# PCB0M3_1C.net
KiCad netlist of a schematic drawn in EAGLE
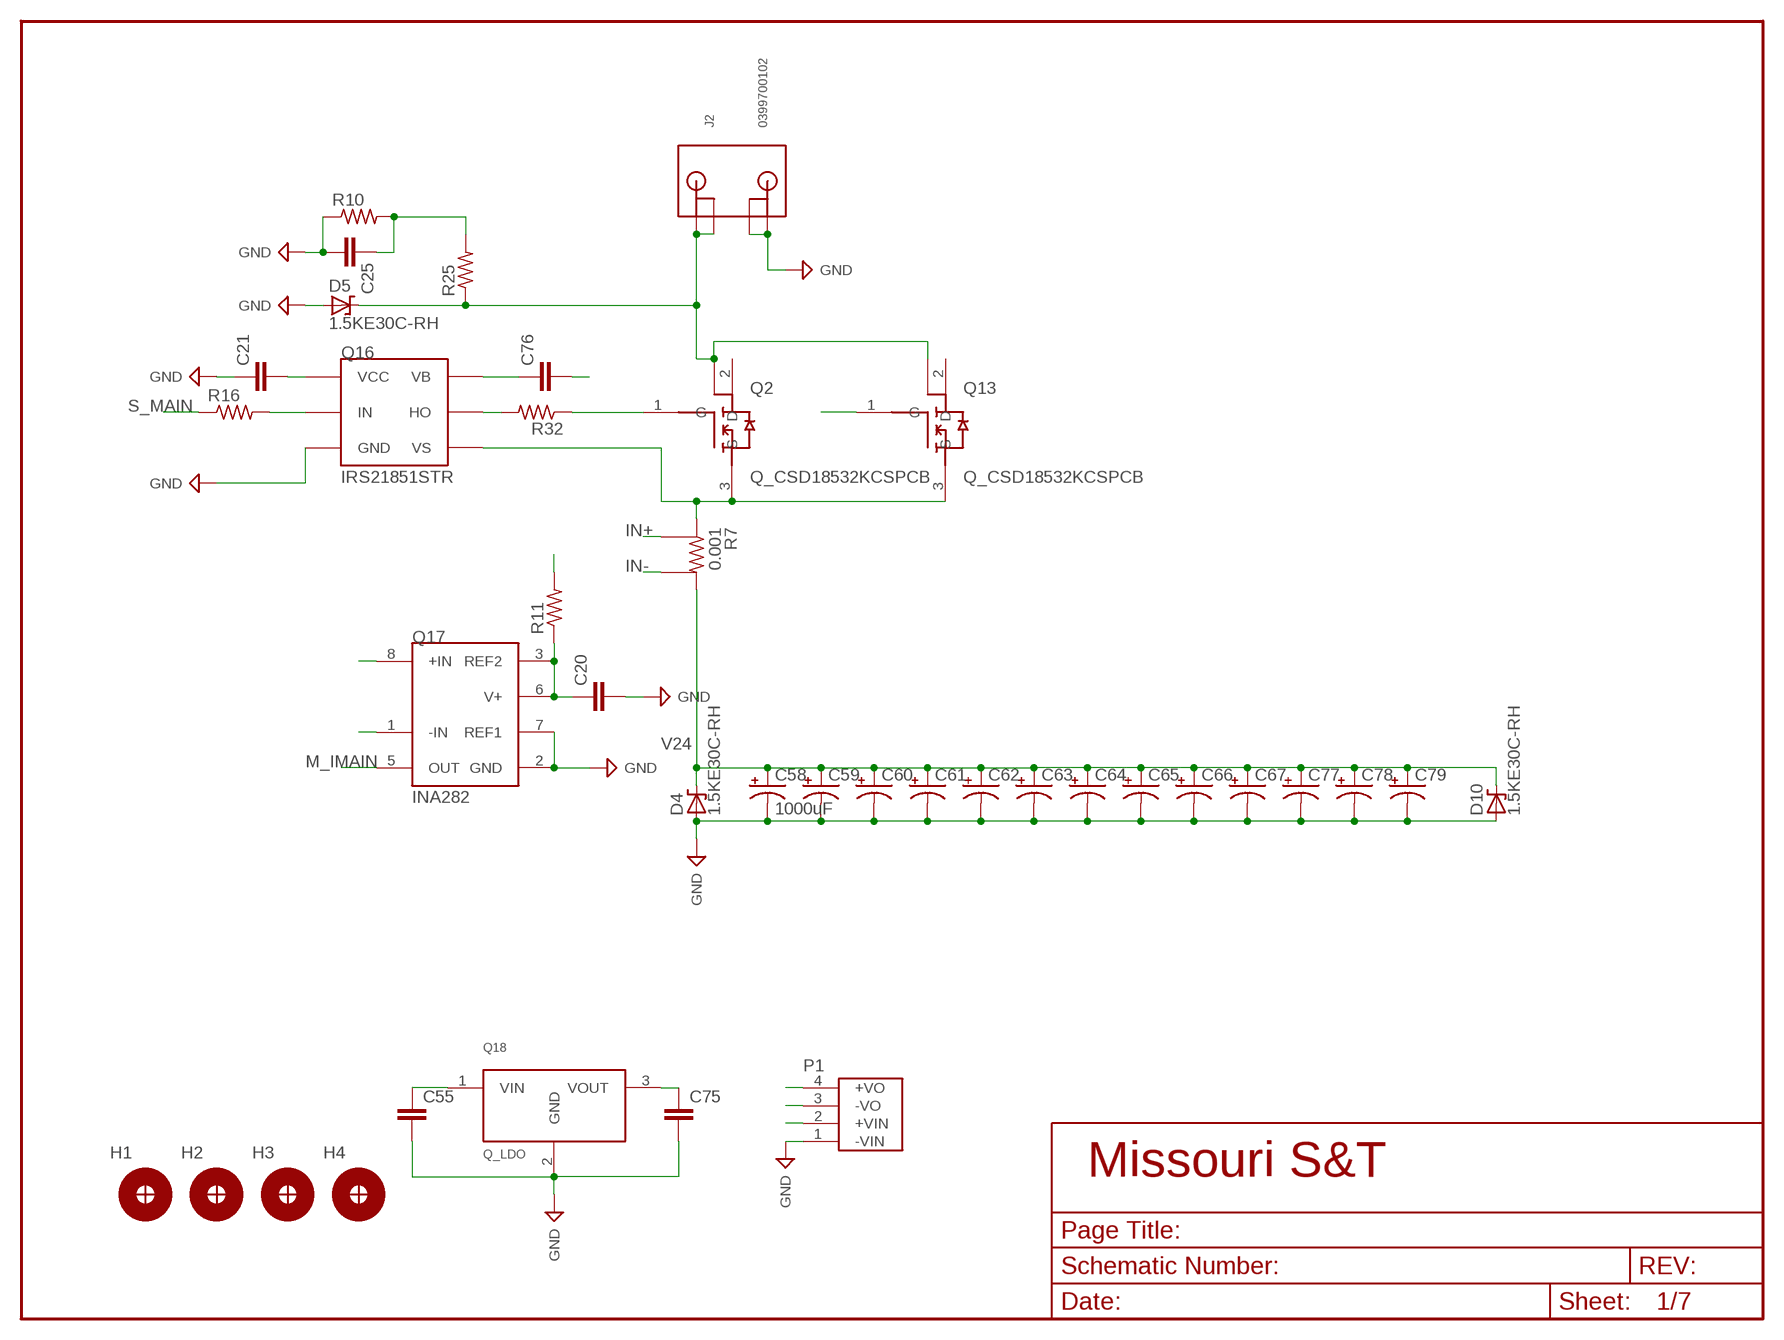
[diagram p0: schematic, sheet 1]
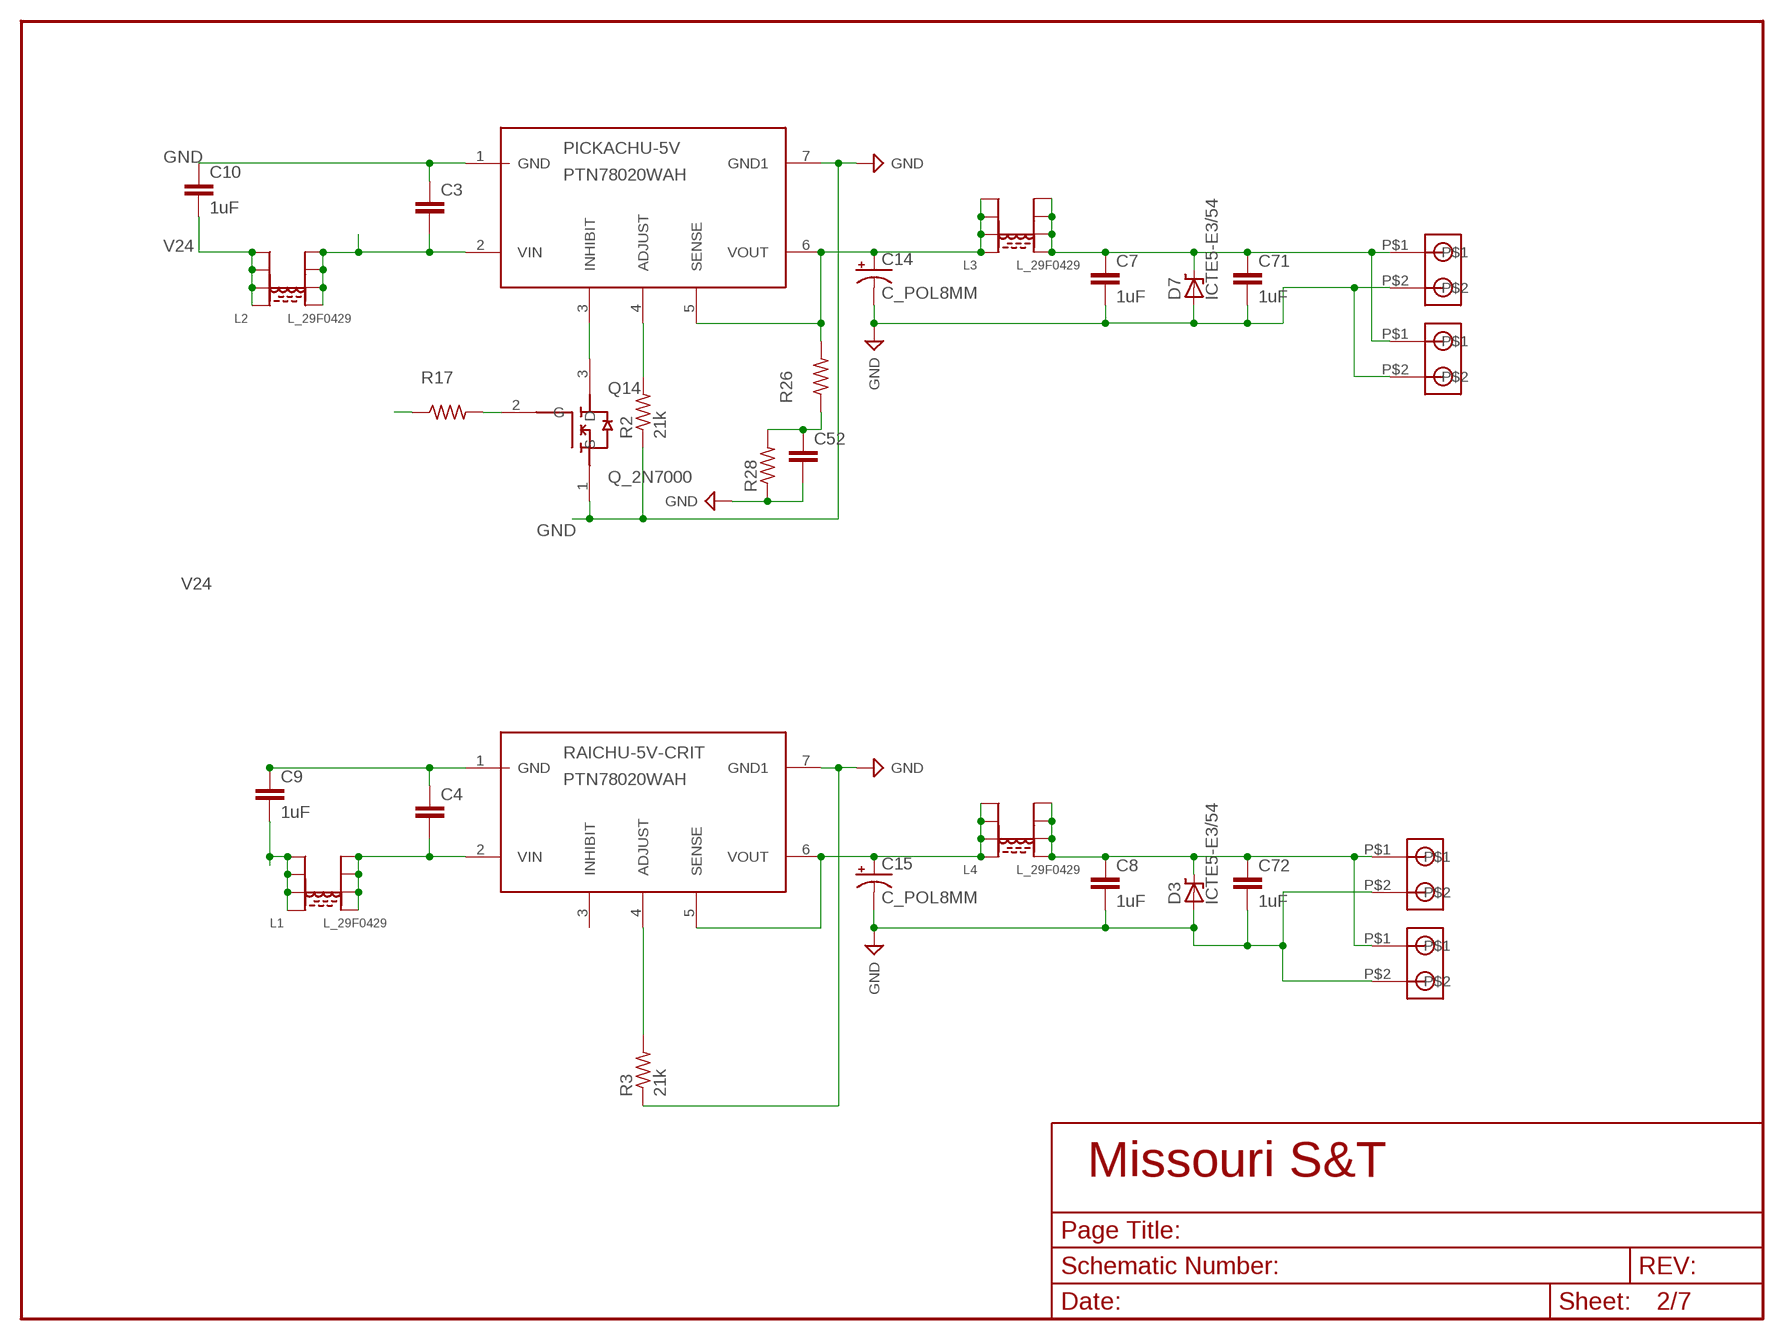
[diagram p1: schematic, sheet 2]
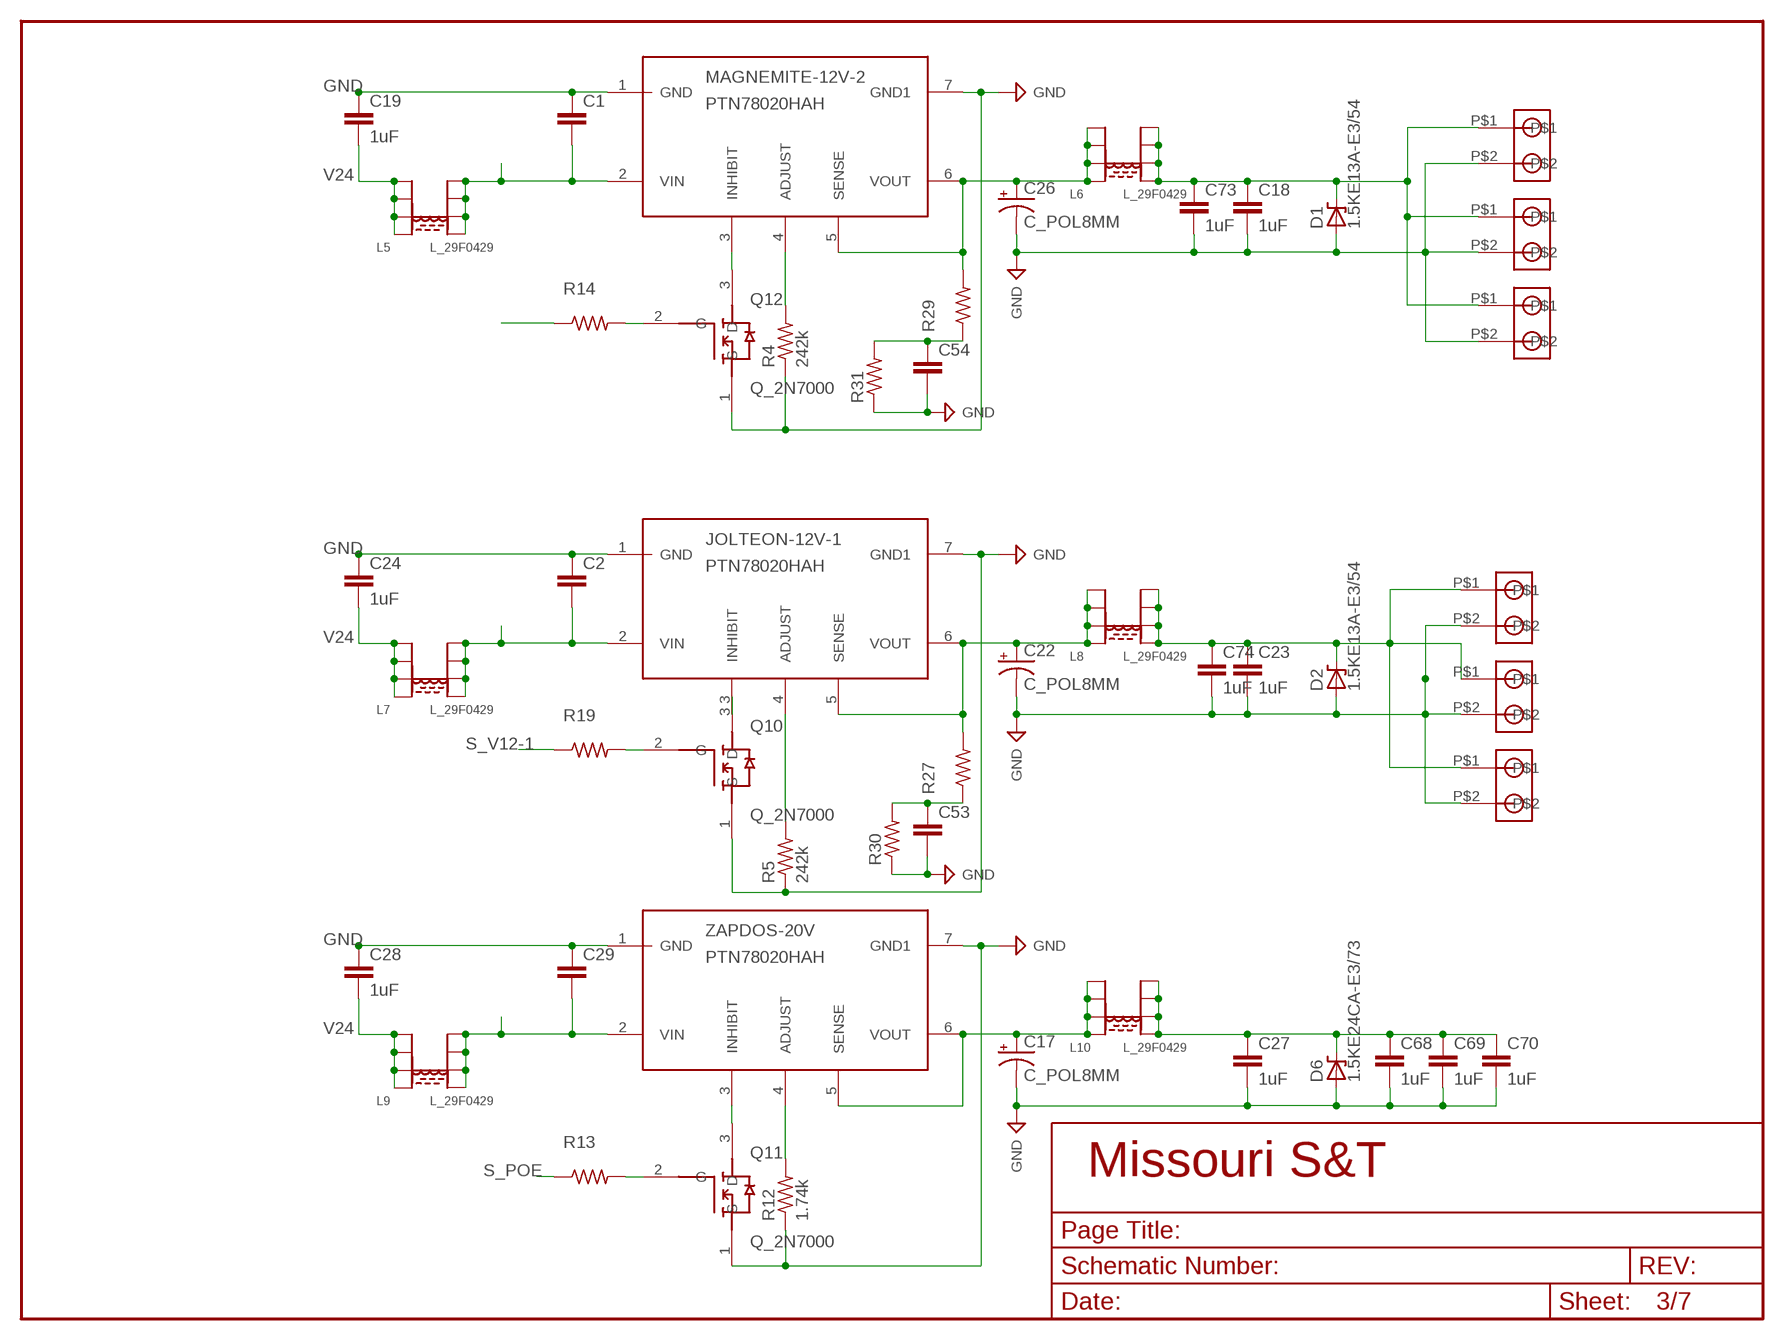
[diagram p2: schematic, sheet 3]
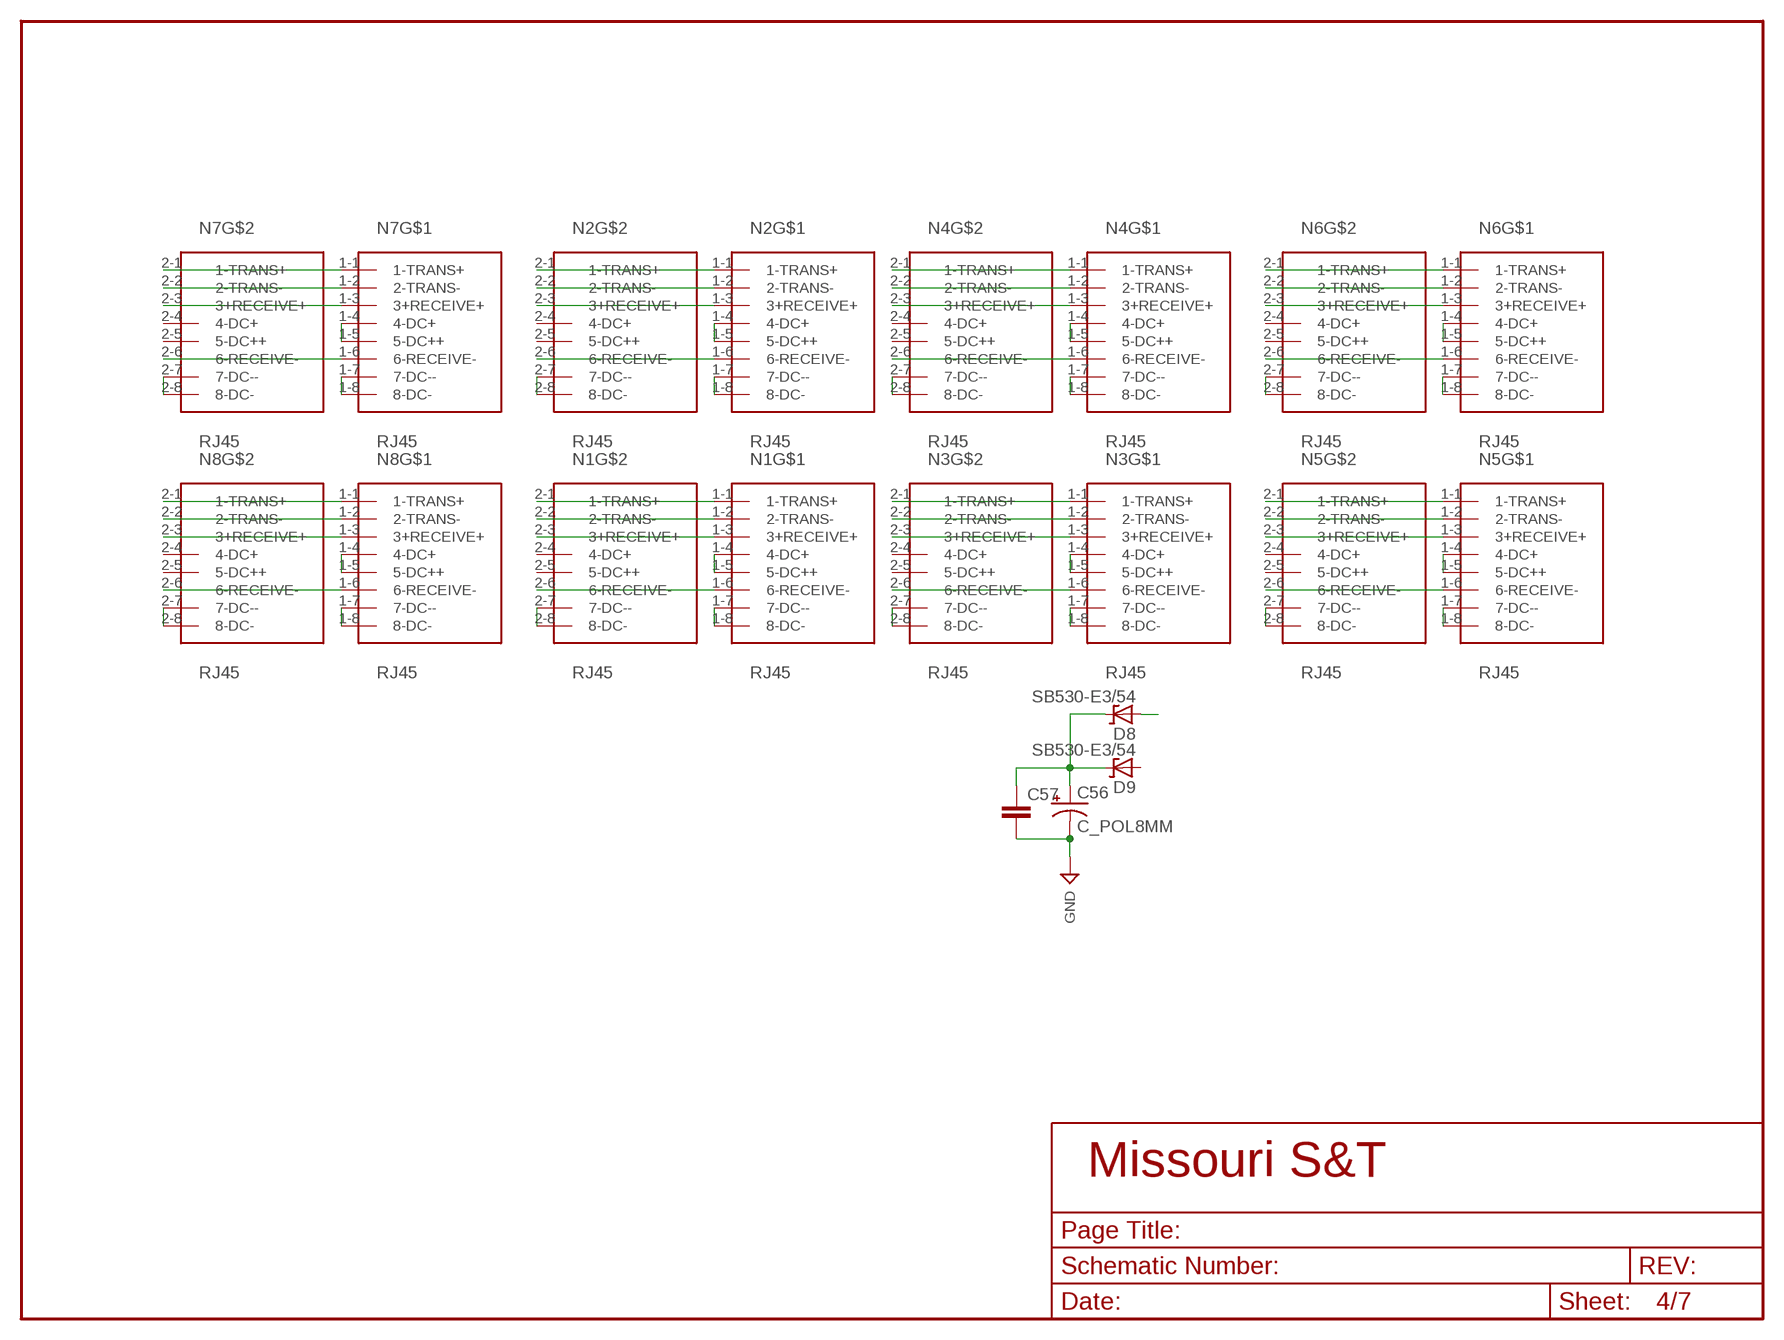
[diagram p3: schematic, sheet 4]
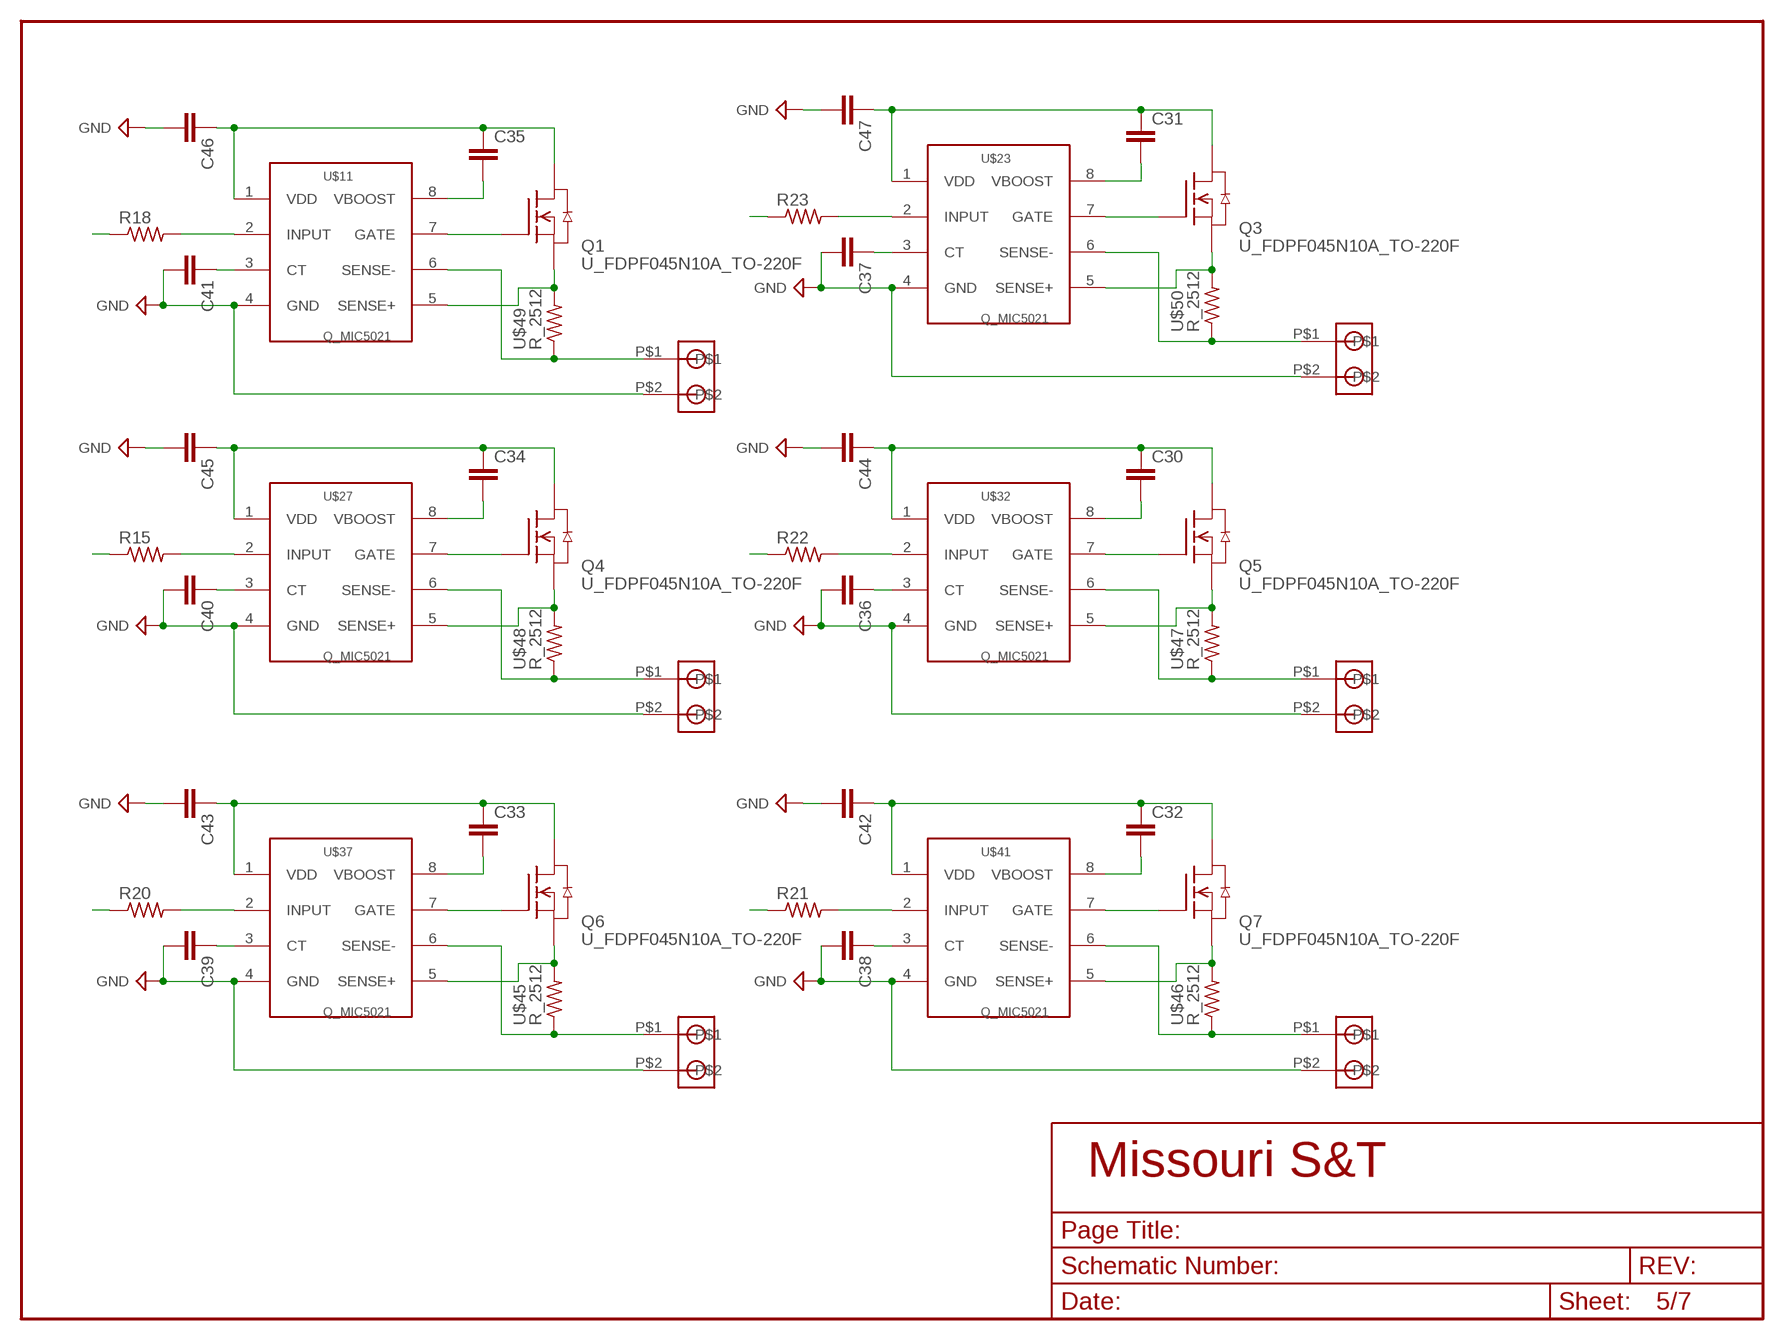
[diagram p4: schematic, sheet 5]
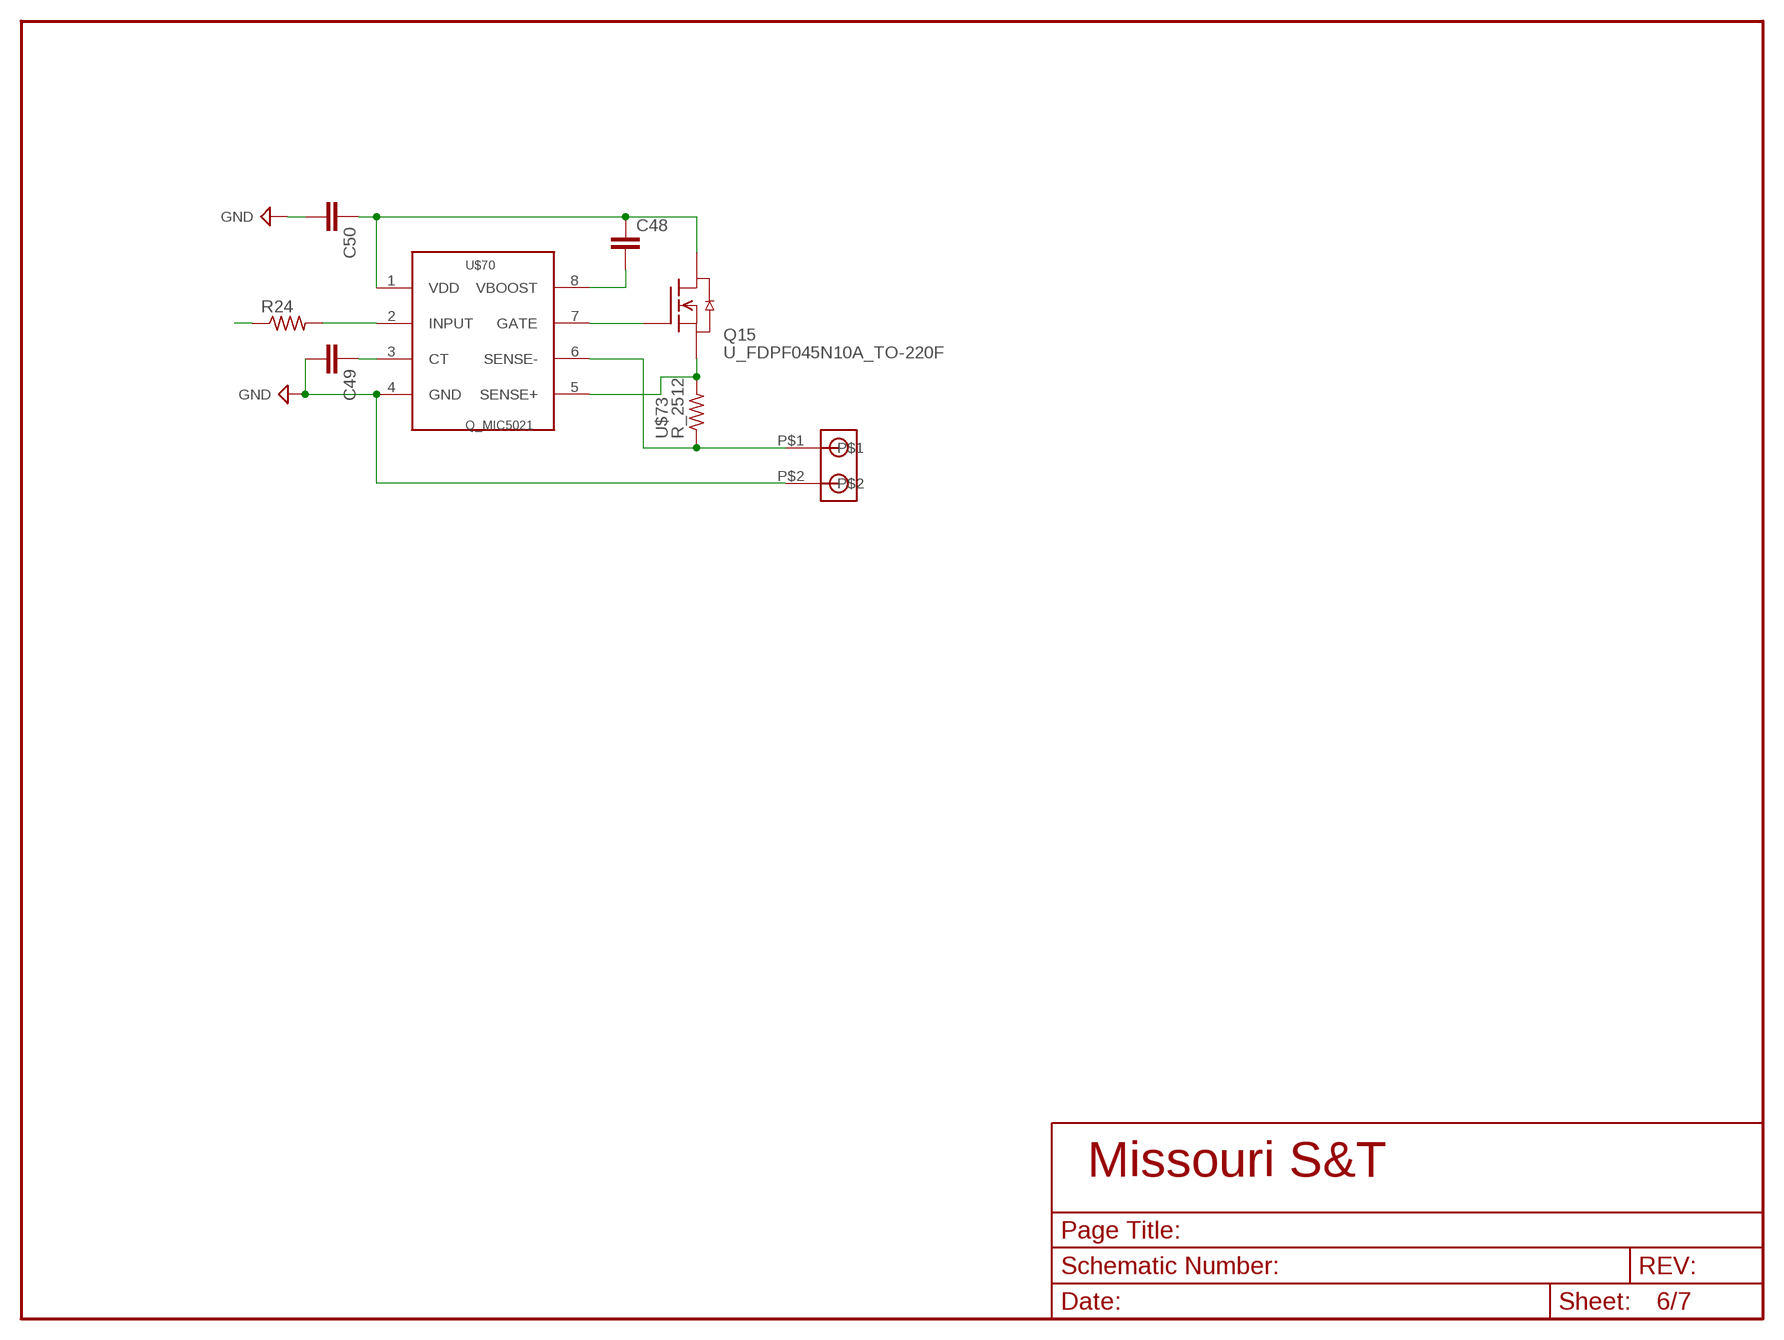
[diagram p5: schematic, sheet 6]
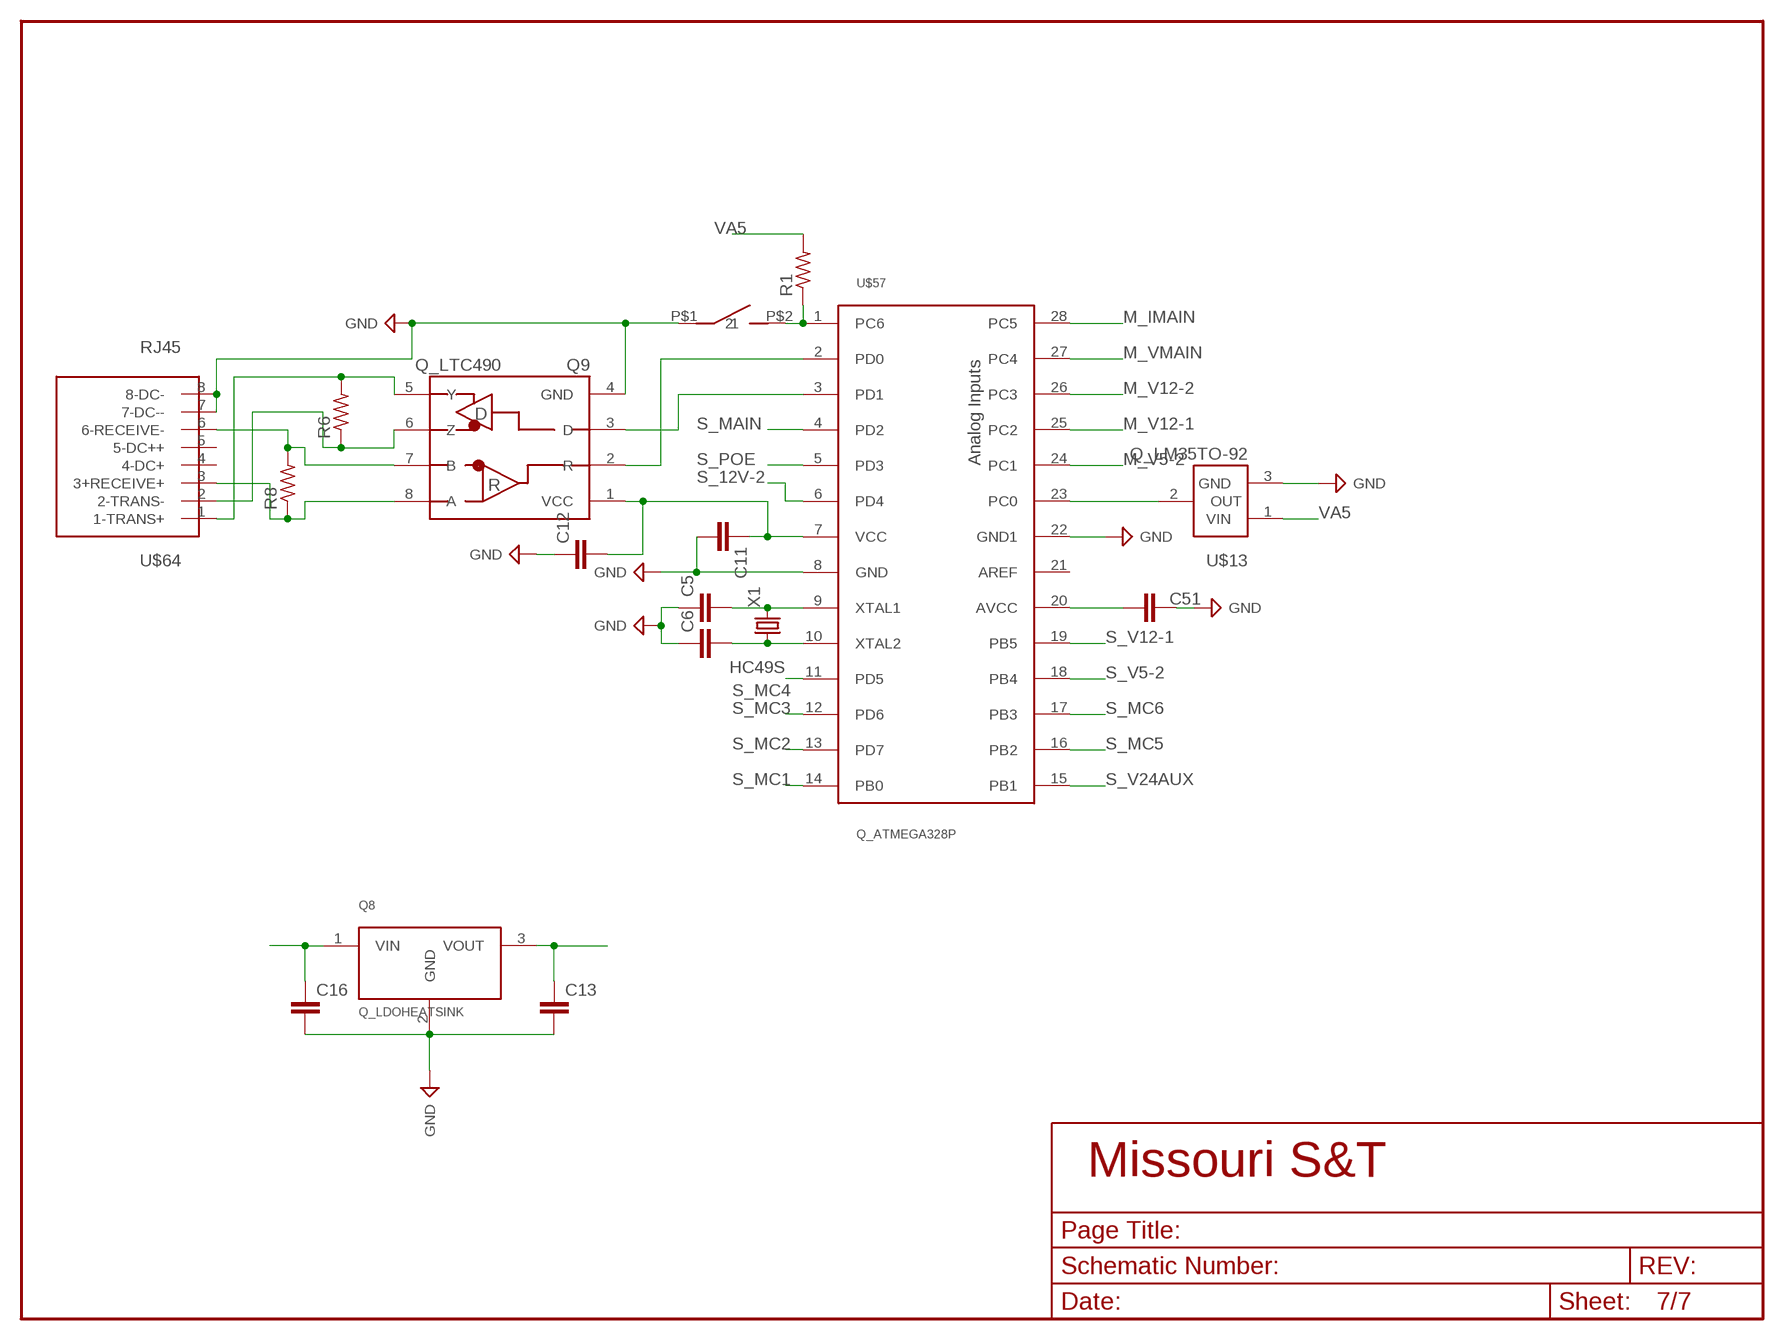
[diagram p6: schematic, sheet 7]

(export (version "E")
  (design (tool "Eeschema 10.0.6"))
  (components
    (comp (ref "C3")
      (value "C_CAP_1206")
      (footprint "eagle-import:C_1206")
      (libsource (lib "eagle-import") (part "C_CAP_1206"))
    )
    (comp (ref "C4")
      (value "C_CAP_1206")
      (footprint "eagle-import:C_1206")
      (libsource (lib "eagle-import") (part "C_CAP_1206"))
    )
    (comp (ref "C7")
      (value "1uF")
      (footprint "eagle-import:C_1206")
      (libsource (lib "eagle-import") (part "C_CAP_1206"))
    )
    (comp (ref "C8")
      (value "1uF")
      (footprint "eagle-import:C_1206")
      (libsource (lib "eagle-import") (part "C_CAP_1206"))
    )
    (comp (ref "C9")
      (value "1uF")
      (footprint "eagle-import:C_1206")
      (libsource (lib "eagle-import") (part "C_CAP_1206"))
    )
    (comp (ref "C10")
      (value "1uF")
      (footprint "eagle-import:C_1206")
      (libsource (lib "eagle-import") (part "C_CAP_1206"))
    )
    (comp (ref "C14")
      (value "C_POL8MM")
      (footprint "eagle-import:C_8MM")
      (libsource (lib "eagle-import") (part "C_POL8MM"))
    )
    (comp (ref "C15")
      (value "C_POL8MM")
      (footprint "eagle-import:C_8MM")
      (libsource (lib "eagle-import") (part "C_POL8MM"))
    )
    (comp (ref "C52")
      (value "C_CAP_1206")
      (footprint "eagle-import:C_1206")
      (libsource (lib "eagle-import") (part "C_CAP_1206"))
    )
    (comp (ref "C71")
      (value "1uF")
      (footprint "eagle-import:C_1206")
      (libsource (lib "eagle-import") (part "C_CAP_1206"))
    )
    (comp (ref "C72")
      (value "1uF")
      (footprint "eagle-import:C_1206")
      (libsource (lib "eagle-import") (part "C_CAP_1206"))
    )
    (comp (ref "D3")
      (value "ICTE5-E3/54")
      (footprint "eagle-import:DIODE_D3.5MM_LS15.24MM")
      (libsource (lib "eagle-import") (part "D_1.5KE480A_D3.5MM_LS15.24MM"))
    )
    (comp (ref "D7")
      (value "ICTE5-E3/54")
      (footprint "eagle-import:DIODE_D3.5MM_LS15.24MM")
      (libsource (lib "eagle-import") (part "D_1.5KE480A_D3.5MM_LS15.24MM"))
    )
    (comp (ref "L1")
      (value "L_29F0429")
      (footprint "eagle-import:L_29F0429")
      (libsource (lib "eagle-import") (part "L_29F0429"))
    )
    (comp (ref "L2")
      (value "L_29F0429")
      (footprint "eagle-import:L_29F0429")
      (libsource (lib "eagle-import") (part "L_29F0429"))
    )
    (comp (ref "L3")
      (value "L_29F0429")
      (footprint "eagle-import:L_29F0429")
      (libsource (lib "eagle-import") (part "L_29F0429"))
    )
    (comp (ref "L4")
      (value "L_29F0429")
      (footprint "eagle-import:L_29F0429")
      (libsource (lib "eagle-import") (part "L_29F0429"))
    )
    (comp (ref "PICKACHU-5V")
      (value "PTN78020WAH")
      (footprint "eagle-import:R_PDSS-T7")
      (libsource (lib "eagle-import") (part "Q_PTN78020"))
    )
    (comp (ref "Q14")
      (value "Q_2N7000")
      (footprint "eagle-import:TO-92-3")
      (libsource (lib "eagle-import") (part "Q_2N7000"))
    )
    (comp (ref "R2")
      (value "21k")
      (footprint "eagle-import:R_1_4W")
      (libsource (lib "eagle-import") (part "R_1/4W"))
    )
    (comp (ref "R3")
      (value "21k")
      (footprint "eagle-import:R_1_4W")
      (libsource (lib "eagle-import") (part "R_1/4W"))
    )
    (comp (ref "R17")
      (value "R_1/4WL")
      (footprint "eagle-import:R_1_4WL")
      (libsource (lib "eagle-import") (part "R_1/4WL"))
    )
    (comp (ref "R26")
      (value "R_1/4WL")
      (footprint "eagle-import:R_1_4WL")
      (libsource (lib "eagle-import") (part "R_1/4WL"))
    )
    (comp (ref "R28")
      (value "R_RES_1206")
      (footprint "eagle-import:R_1206")
      (libsource (lib "eagle-import") (part "R_RES_1206"))
    )
    (comp (ref "RAICHU-5V-CRIT")
      (value "PTN78020WAH")
      (footprint "eagle-import:R_PDSS-T7")
      (libsource (lib "eagle-import") (part "Q_PTN78020"))
    )
    (comp (ref "U$52")
      (value "J_1546074-2282834-2")
      (footprint "eagle-import:J_2.54MM")
      (libsource (lib "eagle-import") (part "J_1546074-2282834-2"))
    )
    (comp (ref "U$53")
      (value "J_1546074-2282834-2")
      (footprint "eagle-import:J_2.54MM")
      (libsource (lib "eagle-import") (part "J_1546074-2282834-2"))
    )
    (comp (ref "U$54")
      (value "J_1546074-2282834-2")
      (footprint "eagle-import:J_2.54MM")
      (libsource (lib "eagle-import") (part "J_1546074-2282834-2"))
    )
    (comp (ref "U$55")
      (value "J_1546074-2282834-2")
      (footprint "eagle-import:J_2.54MM")
      (libsource (lib "eagle-import") (part "J_1546074-2282834-2"))
    )
    (comp (ref "C30")
      (value "C_CAP_1206")
      (footprint "eagle-import:C_1206")
      (libsource (lib "eagle-import") (part "C_CAP_1206"))
    )
    (comp (ref "C31")
      (value "C_CAP_1206")
      (footprint "eagle-import:C_1206")
      (libsource (lib "eagle-import") (part "C_CAP_1206"))
    )
    (comp (ref "C32")
      (value "C_CAP_1206")
      (footprint "eagle-import:C_1206")
      (libsource (lib "eagle-import") (part "C_CAP_1206"))
    )
    (comp (ref "C33")
      (value "C_CAP_1206")
      (footprint "eagle-import:C_1206")
      (libsource (lib "eagle-import") (part "C_CAP_1206"))
    )
    (comp (ref "C34")
      (value "C_CAP_1206")
      (footprint "eagle-import:C_1206")
      (libsource (lib "eagle-import") (part "C_CAP_1206"))
    )
    (comp (ref "C35")
      (value "C_CAP_1206")
      (footprint "eagle-import:C_1206")
      (libsource (lib "eagle-import") (part "C_CAP_1206"))
    )
    (comp (ref "C36")
      (value "C_CAP_1206")
      (footprint "eagle-import:C_1206")
      (libsource (lib "eagle-import") (part "C_CAP_1206"))
    )
    (comp (ref "C37")
      (value "C_CAP_1206")
      (footprint "eagle-import:C_1206")
      (libsource (lib "eagle-import") (part "C_CAP_1206"))
    )
    (comp (ref "C38")
      (value "C_CAP_1206")
      (footprint "eagle-import:C_1206")
      (libsource (lib "eagle-import") (part "C_CAP_1206"))
    )
    (comp (ref "C39")
      (value "C_CAP_1206")
      (footprint "eagle-import:C_1206")
      (libsource (lib "eagle-import") (part "C_CAP_1206"))
    )
    (comp (ref "C40")
      (value "C_CAP_1206")
      (footprint "eagle-import:C_1206")
      (libsource (lib "eagle-import") (part "C_CAP_1206"))
    )
    (comp (ref "C41")
      (value "C_CAP_1206")
      (footprint "eagle-import:C_1206")
      (libsource (lib "eagle-import") (part "C_CAP_1206"))
    )
    (comp (ref "C42")
      (value "C_CAP_1206")
      (footprint "eagle-import:C_1206")
      (libsource (lib "eagle-import") (part "C_CAP_1206"))
    )
    (comp (ref "C43")
      (value "C_CAP_1206")
      (footprint "eagle-import:C_1206")
      (libsource (lib "eagle-import") (part "C_CAP_1206"))
    )
    (comp (ref "C44")
      (value "C_CAP_1206")
      (footprint "eagle-import:C_1206")
      (libsource (lib "eagle-import") (part "C_CAP_1206"))
    )
    (comp (ref "C45")
      (value "C_CAP_1206")
      (footprint "eagle-import:C_1206")
      (libsource (lib "eagle-import") (part "C_CAP_1206"))
    )
    (comp (ref "C46")
      (value "C_CAP_1206")
      (footprint "eagle-import:C_1206")
      (libsource (lib "eagle-import") (part "C_CAP_1206"))
    )
    (comp (ref "C47")
      (value "C_CAP_1206")
      (footprint "eagle-import:C_1206")
      (libsource (lib "eagle-import") (part "C_CAP_1206"))
    )
    (comp (ref "Q1")
      (value "U_FDPF045N10A_TO-220F")
      (footprint "eagle-import:TO220F")
      (libsource (lib "eagle-import") (part "U_FDPF045N10A_TO-220F"))
    )
    (comp (ref "Q3")
      (value "U_FDPF045N10A_TO-220F")
      (footprint "eagle-import:TO220F")
      (libsource (lib "eagle-import") (part "U_FDPF045N10A_TO-220F"))
    )
    (comp (ref "Q4")
      (value "U_FDPF045N10A_TO-220F")
      (footprint "eagle-import:TO220F")
      (libsource (lib "eagle-import") (part "U_FDPF045N10A_TO-220F"))
    )
    (comp (ref "Q5")
      (value "U_FDPF045N10A_TO-220F")
      (footprint "eagle-import:TO220F")
      (libsource (lib "eagle-import") (part "U_FDPF045N10A_TO-220F"))
    )
    (comp (ref "Q6")
      (value "U_FDPF045N10A_TO-220F")
      (footprint "eagle-import:TO220F")
      (libsource (lib "eagle-import") (part "U_FDPF045N10A_TO-220F"))
    )
    (comp (ref "Q7")
      (value "U_FDPF045N10A_TO-220F")
      (footprint "eagle-import:TO220F")
      (libsource (lib "eagle-import") (part "U_FDPF045N10A_TO-220F"))
    )
    (comp (ref "R15")
      (value "R_RES_1206")
      (footprint "eagle-import:R_1206")
      (libsource (lib "eagle-import") (part "R_RES_1206"))
    )
    (comp (ref "R18")
      (value "R_RES_1206")
      (footprint "eagle-import:R_1206")
      (libsource (lib "eagle-import") (part "R_RES_1206"))
    )
    (comp (ref "R20")
      (value "R_RES_1206")
      (footprint "eagle-import:R_1206")
      (libsource (lib "eagle-import") (part "R_RES_1206"))
    )
    (comp (ref "R21")
      (value "R_RES_1206")
      (footprint "eagle-import:R_1206")
      (libsource (lib "eagle-import") (part "R_RES_1206"))
    )
    (comp (ref "R22")
      (value "R_RES_1206")
      (footprint "eagle-import:R_1206")
      (libsource (lib "eagle-import") (part "R_RES_1206"))
    )
    (comp (ref "R23")
      (value "R_RES_1206")
      (footprint "eagle-import:R_1206")
      (libsource (lib "eagle-import") (part "R_RES_1206"))
    )
    (comp (ref "U$11")
      (value "Q_MIC5021")
      (footprint "eagle-import:DIP8")
      (libsource (lib "eagle-import") (part "Q_MIC5021"))
    )
    (comp (ref "U$14")
      (value "J_1546074-2")
      (footprint "eagle-import:THERM_BLOCK_2")
      (libsource (lib "eagle-import") (part "J_1546074-2"))
    )
    (comp (ref "U$23")
      (value "Q_MIC5021")
      (footprint "eagle-import:DIP8")
      (libsource (lib "eagle-import") (part "Q_MIC5021"))
    )
    (comp (ref "U$26")
      (value "J_1546074-2")
      (footprint "eagle-import:THERM_BLOCK_2")
      (libsource (lib "eagle-import") (part "J_1546074-2"))
    )
    (comp (ref "U$27")
      (value "Q_MIC5021")
      (footprint "eagle-import:DIP8")
      (libsource (lib "eagle-import") (part "Q_MIC5021"))
    )
    (comp (ref "U$31")
      (value "J_1546074-2")
      (footprint "eagle-import:THERM_BLOCK_2")
      (libsource (lib "eagle-import") (part "J_1546074-2"))
    )
    (comp (ref "U$32")
      (value "Q_MIC5021")
      (footprint "eagle-import:DIP8")
      (libsource (lib "eagle-import") (part "Q_MIC5021"))
    )
    (comp (ref "U$36")
      (value "J_1546074-2")
      (footprint "eagle-import:THERM_BLOCK_2")
      (libsource (lib "eagle-import") (part "J_1546074-2"))
    )
    (comp (ref "U$37")
      (value "Q_MIC5021")
      (footprint "eagle-import:DIP8")
      (libsource (lib "eagle-import") (part "Q_MIC5021"))
    )
    (comp (ref "U$40")
      (value "J_1546074-2")
      (footprint "eagle-import:THERM_BLOCK_2")
      (libsource (lib "eagle-import") (part "J_1546074-2"))
    )
    (comp (ref "U$41")
      (value "Q_MIC5021")
      (footprint "eagle-import:DIP8")
      (libsource (lib "eagle-import") (part "Q_MIC5021"))
    )
    (comp (ref "U$44")
      (value "J_1546074-2")
      (footprint "eagle-import:THERM_BLOCK_2")
      (libsource (lib "eagle-import") (part "J_1546074-2"))
    )
    (comp (ref "U$45")
      (value "R_2512")
      (footprint "eagle-import:R_2512")
      (libsource (lib "eagle-import") (part "R_2512"))
    )
    (comp (ref "U$46")
      (value "R_2512")
      (footprint "eagle-import:R_2512")
      (libsource (lib "eagle-import") (part "R_2512"))
    )
    (comp (ref "U$47")
      (value "R_2512")
      (footprint "eagle-import:R_2512")
      (libsource (lib "eagle-import") (part "R_2512"))
    )
    (comp (ref "U$48")
      (value "R_2512")
      (footprint "eagle-import:R_2512")
      (libsource (lib "eagle-import") (part "R_2512"))
    )
    (comp (ref "U$49")
      (value "R_2512")
      (footprint "eagle-import:R_2512")
      (libsource (lib "eagle-import") (part "R_2512"))
    )
    (comp (ref "U$50")
      (value "R_2512")
      (footprint "eagle-import:R_2512")
      (libsource (lib "eagle-import") (part "R_2512"))
    )
    (comp (ref "C20")
      (value "C_CAP_1206")
      (footprint "eagle-import:C_1206")
      (libsource (lib "eagle-import") (part "C_CAP_1206"))
    )
    (comp (ref "C21")
      (value "C_CAP_1206")
      (footprint "eagle-import:C_1206")
      (libsource (lib "eagle-import") (part "C_CAP_1206"))
    )
    (comp (ref "C25")
      (value "C_CAP_1206")
      (footprint "eagle-import:C_1206")
      (libsource (lib "eagle-import") (part "C_CAP_1206"))
    )
    (comp (ref "C55")
      (value "C_CAP_1206")
      (footprint "eagle-import:C_1206")
      (libsource (lib "eagle-import") (part "C_CAP_1206"))
    )
    (comp (ref "C58")
      (value "1000uF")
      (footprint "eagle-import:C_10MM")
      (libsource (lib "eagle-import") (part "C_POL10MM"))
    )
    (comp (ref "C59")
      (value "C_POL10MM")
      (footprint "eagle-import:C_10MM")
      (libsource (lib "eagle-import") (part "C_POL10MM"))
    )
    (comp (ref "C60")
      (value "C_POL10MM")
      (footprint "eagle-import:C_10MM")
      (libsource (lib "eagle-import") (part "C_POL10MM"))
    )
    (comp (ref "C61")
      (value "C_POL10MM")
      (footprint "eagle-import:C_10MM")
      (libsource (lib "eagle-import") (part "C_POL10MM"))
    )
    (comp (ref "C62")
      (value "C_POL10MM")
      (footprint "eagle-import:C_10MM")
      (libsource (lib "eagle-import") (part "C_POL10MM"))
    )
    (comp (ref "C63")
      (value "C_POL10MM")
      (footprint "eagle-import:C_10MM")
      (libsource (lib "eagle-import") (part "C_POL10MM"))
    )
    (comp (ref "C64")
      (value "C_POL10MM")
      (footprint "eagle-import:C_10MM")
      (libsource (lib "eagle-import") (part "C_POL10MM"))
    )
    (comp (ref "C65")
      (value "C_POL10MM")
      (footprint "eagle-import:C_10MM")
      (libsource (lib "eagle-import") (part "C_POL10MM"))
    )
    (comp (ref "C66")
      (value "C_POL10MM")
      (footprint "eagle-import:C_10MM")
      (libsource (lib "eagle-import") (part "C_POL10MM"))
    )
    (comp (ref "C67")
      (value "C_POL10MM")
      (footprint "eagle-import:C_10MM")
      (libsource (lib "eagle-import") (part "C_POL10MM"))
    )
    (comp (ref "C75")
      (value "C_CAP_1206")
      (footprint "eagle-import:C_1206")
      (libsource (lib "eagle-import") (part "C_CAP_1206"))
    )
    (comp (ref "C76")
      (value "C_CAP_1206")
      (footprint "eagle-import:C_1206")
      (libsource (lib "eagle-import") (part "C_CAP_1206"))
    )
    (comp (ref "C77")
      (value "C_POL10MM")
      (footprint "eagle-import:C_10MM")
      (libsource (lib "eagle-import") (part "C_POL10MM"))
    )
    (comp (ref "C78")
      (value "C_POL10MM")
      (footprint "eagle-import:C_10MM")
      (libsource (lib "eagle-import") (part "C_POL10MM"))
    )
    (comp (ref "C79")
      (value "C_POL10MM")
      (footprint "eagle-import:C_10MM")
      (libsource (lib "eagle-import") (part "C_POL10MM"))
    )
    (comp (ref "D4")
      (value "1.5KE30C-RH")
      (footprint "eagle-import:DIODE_D3.5MM_LS15.24MM")
      (libsource (lib "eagle-import") (part "D_1.5KE480A_D3.5MM_LS15.24MM"))
    )
    (comp (ref "D5")
      (value "1.5KE30C-RH")
      (footprint "eagle-import:DIODE_D3.5MM_LS15.24MM")
      (libsource (lib "eagle-import") (part "D_1.5KE480A_D3.5MM_LS15.24MM"))
    )
    (comp (ref "D10")
      (value "1.5KE30C-RH")
      (footprint "eagle-import:DIODE_D3.5MM_LS15.24MM")
      (libsource (lib "eagle-import") (part "D_1.5KE480A_D3.5MM_LS15.24MM"))
    )
    (comp (ref "H1")
      (value "H_MNTHOLE_#8")
      (footprint "eagle-import:H_MNTHOLE_#8")
      (libsource (lib "eagle-import") (part "H_MNTHOLE_#8"))
    )
    (comp (ref "H2")
      (value "H_MNTHOLE_#8")
      (footprint "eagle-import:H_MNTHOLE_#8")
      (libsource (lib "eagle-import") (part "H_MNTHOLE_#8"))
    )
    (comp (ref "H3")
      (value "H_MNTHOLE_#8")
      (footprint "eagle-import:H_MNTHOLE_#8")
      (libsource (lib "eagle-import") (part "H_MNTHOLE_#8"))
    )
    (comp (ref "H4")
      (value "H_MNTHOLE_#8")
      (footprint "eagle-import:H_MNTHOLE_#8")
      (libsource (lib "eagle-import") (part "H_MNTHOLE_#8"))
    )
    (comp (ref "J2")
      (value "0399700102")
      (footprint "eagle-import:J_2CONHC")
      (libsource (lib "eagle-import") (part "J_0399700102"))
    )
    (comp (ref "P1")
      (value "TME1215S")
      (footprint "eagle-import:TME1215S")
      (libsource (lib "eagle-import") (part "TME1215S"))
    )
    (comp (ref "Q2")
      (value "Q_CSD18532KCSPCB")
      (footprint "eagle-import:TO-220-FLAT")
      (libsource (lib "eagle-import") (part "Q_CSD18532KCSPCB"))
    )
    (comp (ref "Q13")
      (value "Q_CSD18532KCSPCB")
      (footprint "eagle-import:TO-220-FLAT")
      (libsource (lib "eagle-import") (part "Q_CSD18532KCSPCB"))
    )
    (comp (ref "Q16")
      (value "IRS21851STR")
      (footprint "eagle-import:SOIC8")
      (libsource (lib "eagle-import") (part "Q_IRS21851STR"))
    )
    (comp (ref "Q17")
      (value "INA282")
      (footprint "eagle-import:SOIC8")
      (libsource (lib "eagle-import") (part "Q_INA28"))
    )
    (comp (ref "Q18")
      (value "Q_LDO")
      (footprint "eagle-import:TO-220")
      (libsource (lib "eagle-import") (part "Q_LDO"))
    )
    (comp (ref "R7")
      (value "0.001")
      (footprint "eagle-import:R_FC4L")
      (libsource (lib "eagle-import") (part "R_FC4L110R001JER"))
    )
    (comp (ref "R10")
      (value "R_RES_1206")
      (footprint "eagle-import:R_1206")
      (libsource (lib "eagle-import") (part "R_RES_1206"))
    )
    (comp (ref "R11")
      (value "R_1/4W")
      (footprint "eagle-import:R_1_4W")
      (libsource (lib "eagle-import") (part "R_1/4W"))
    )
    (comp (ref "R16")
      (value "R_RES_1206")
      (footprint "eagle-import:R_1206")
      (libsource (lib "eagle-import") (part "R_RES_1206"))
    )
    (comp (ref "R25")
      (value "R_1/4W")
      (footprint "eagle-import:R_1_4W")
      (libsource (lib "eagle-import") (part "R_1/4W"))
    )
    (comp (ref "R32")
      (value "R_RES_1206")
      (footprint "eagle-import:R_1206")
      (libsource (lib "eagle-import") (part "R_RES_1206"))
    )
    (comp (ref "C1")
      (value "C_CAP_1206")
      (footprint "eagle-import:C_1206")
      (libsource (lib "eagle-import") (part "C_CAP_1206"))
    )
    (comp (ref "C2")
      (value "C_CAP_1206")
      (footprint "eagle-import:C_1206")
      (libsource (lib "eagle-import") (part "C_CAP_1206"))
    )
    (comp (ref "C17")
      (value "C_POL8MM")
      (footprint "eagle-import:C_8MM")
      (libsource (lib "eagle-import") (part "C_POL8MM"))
    )
    (comp (ref "C18")
      (value "1uF")
      (footprint "eagle-import:C_1206")
      (libsource (lib "eagle-import") (part "C_CAP_1206"))
    )
    (comp (ref "C19")
      (value "1uF")
      (footprint "eagle-import:C_1206")
      (libsource (lib "eagle-import") (part "C_CAP_1206"))
    )
    (comp (ref "C22")
      (value "C_POL8MM")
      (footprint "eagle-import:C_8MM")
      (libsource (lib "eagle-import") (part "C_POL8MM"))
    )
    (comp (ref "C23")
      (value "1uF")
      (footprint "eagle-import:C_1206")
      (libsource (lib "eagle-import") (part "C_CAP_1206"))
    )
    (comp (ref "C24")
      (value "1uF")
      (footprint "eagle-import:C_1206")
      (libsource (lib "eagle-import") (part "C_CAP_1206"))
    )
    (comp (ref "C26")
      (value "C_POL8MM")
      (footprint "eagle-import:C_8MM")
      (libsource (lib "eagle-import") (part "C_POL8MM"))
    )
    (comp (ref "C27")
      (value "1uF")
      (footprint "eagle-import:C_1206")
      (libsource (lib "eagle-import") (part "C_CAP_1206"))
    )
    (comp (ref "C28")
      (value "1uF")
      (footprint "eagle-import:C_1206")
      (libsource (lib "eagle-import") (part "C_CAP_1206"))
    )
    (comp (ref "C29")
      (value "C_CAP_1206")
      (footprint "eagle-import:C_1206")
      (libsource (lib "eagle-import") (part "C_CAP_1206"))
    )
    (comp (ref "C53")
      (value "C_CAP_1206")
      (footprint "eagle-import:C_1206")
      (libsource (lib "eagle-import") (part "C_CAP_1206"))
    )
    (comp (ref "C54")
      (value "C_CAP_1206")
      (footprint "eagle-import:C_1206")
      (libsource (lib "eagle-import") (part "C_CAP_1206"))
    )
    (comp (ref "C68")
      (value "1uF")
      (footprint "eagle-import:C_1206")
      (libsource (lib "eagle-import") (part "C_CAP_1206"))
    )
    (comp (ref "C69")
      (value "1uF")
      (footprint "eagle-import:C_1206")
      (libsource (lib "eagle-import") (part "C_CAP_1206"))
    )
    (comp (ref "C70")
      (value "1uF")
      (footprint "eagle-import:C_1206")
      (libsource (lib "eagle-import") (part "C_CAP_1206"))
    )
    (comp (ref "C73")
      (value "1uF")
      (footprint "eagle-import:C_1206")
      (libsource (lib "eagle-import") (part "C_CAP_1206"))
    )
    (comp (ref "C74")
      (value "1uF")
      (footprint "eagle-import:C_1206")
      (libsource (lib "eagle-import") (part "C_CAP_1206"))
    )
    (comp (ref "D1")
      (value "1.5KE13A-E3/54")
      (footprint "eagle-import:DIODE_D3.5MM_LS15.24MM")
      (libsource (lib "eagle-import") (part "D_1.5KE480A_D3.5MM_LS15.24MM"))
    )
    (comp (ref "D2")
      (value "1.5KE13A-E3/54")
      (footprint "eagle-import:DIODE_D3.5MM_LS15.24MM")
      (libsource (lib "eagle-import") (part "D_1.5KE480A_D3.5MM_LS15.24MM"))
    )
    (comp (ref "D6")
      (value "1.5KE24CA-E3/73")
      (footprint "eagle-import:DIODE_D3.5MM_LS15.24MM")
      (libsource (lib "eagle-import") (part "D_1.5KE480A_D3.5MM_LS15.24MM"))
    )
    (comp (ref "J3")
      (value "J_1546074-2282834-2")
      (footprint "eagle-import:J_2.54MM")
      (libsource (lib "eagle-import") (part "J_1546074-2282834-2"))
    )
    (comp (ref "J4")
      (value "J_1546074-2282834-2")
      (footprint "eagle-import:J_2.54MM")
      (libsource (lib "eagle-import") (part "J_1546074-2282834-2"))
    )
    (comp (ref "J5")
      (value "J_1546074-2282834-2")
      (footprint "eagle-import:J_2.54MM")
      (libsource (lib "eagle-import") (part "J_1546074-2282834-2"))
    )
    (comp (ref "J6")
      (value "J_1546074-2282834-2")
      (footprint "eagle-import:J_2.54MM")
      (libsource (lib "eagle-import") (part "J_1546074-2282834-2"))
    )
    (comp (ref "J7")
      (value "J_1546074-2282834-2")
      (footprint "eagle-import:J_2.54MM")
      (libsource (lib "eagle-import") (part "J_1546074-2282834-2"))
    )
    (comp (ref "J8")
      (value "J_1546074-2282834-2")
      (footprint "eagle-import:J_2.54MM")
      (libsource (lib "eagle-import") (part "J_1546074-2282834-2"))
    )
    (comp (ref "JOLTEON-12V-1")
      (value "PTN78020HAH")
      (footprint "eagle-import:R_PDSS-T7")
      (libsource (lib "eagle-import") (part "Q_PTN78020"))
    )
    (comp (ref "L5")
      (value "L_29F0429")
      (footprint "eagle-import:L_29F0429")
      (libsource (lib "eagle-import") (part "L_29F0429"))
    )
    (comp (ref "L6")
      (value "L_29F0429")
      (footprint "eagle-import:L_29F0429")
      (libsource (lib "eagle-import") (part "L_29F0429"))
    )
    (comp (ref "L7")
      (value "L_29F0429")
      (footprint "eagle-import:L_29F0429")
      (libsource (lib "eagle-import") (part "L_29F0429"))
    )
    (comp (ref "L8")
      (value "L_29F0429")
      (footprint "eagle-import:L_29F0429")
      (libsource (lib "eagle-import") (part "L_29F0429"))
    )
    (comp (ref "L9")
      (value "L_29F0429")
      (footprint "eagle-import:L_29F0429")
      (libsource (lib "eagle-import") (part "L_29F0429"))
    )
    (comp (ref "L10")
      (value "L_29F0429")
      (footprint "eagle-import:L_29F0429")
      (libsource (lib "eagle-import") (part "L_29F0429"))
    )
    (comp (ref "MAGNEMITE-12V-2")
      (value "PTN78020HAH")
      (footprint "eagle-import:R_PDSS-T7")
      (libsource (lib "eagle-import") (part "Q_PTN78020"))
    )
    (comp (ref "Q10")
      (value "Q_2N7000")
      (footprint "eagle-import:TO-92-3")
      (libsource (lib "eagle-import") (part "Q_2N7000"))
    )
    (comp (ref "Q11")
      (value "Q_2N7000")
      (footprint "eagle-import:TO-92-3")
      (libsource (lib "eagle-import") (part "Q_2N7000"))
    )
    (comp (ref "Q12")
      (value "Q_2N7000")
      (footprint "eagle-import:TO-92-3")
      (libsource (lib "eagle-import") (part "Q_2N7000"))
    )
    (comp (ref "R4")
      (value "242k")
      (footprint "eagle-import:R_1_4W")
      (libsource (lib "eagle-import") (part "R_1/4W"))
    )
    (comp (ref "R5")
      (value "242k")
      (footprint "eagle-import:R_1_4W")
      (libsource (lib "eagle-import") (part "R_1/4W"))
    )
    (comp (ref "R12")
      (value "1.74k")
      (footprint "eagle-import:R_1_4W")
      (libsource (lib "eagle-import") (part "R_1/4W"))
    )
    (comp (ref "R13")
      (value "R_1/4WL")
      (footprint "eagle-import:R_1_4WL")
      (libsource (lib "eagle-import") (part "R_1/4WL"))
    )
    (comp (ref "R14")
      (value "R_1/4WL")
      (footprint "eagle-import:R_1_4WL")
      (libsource (lib "eagle-import") (part "R_1/4WL"))
    )
    (comp (ref "R19")
      (value "R_1/4WL")
      (footprint "eagle-import:R_1_4WL")
      (libsource (lib "eagle-import") (part "R_1/4WL"))
    )
    (comp (ref "R27")
      (value "R_1/4WL")
      (footprint "eagle-import:R_1_4WL")
      (libsource (lib "eagle-import") (part "R_1/4WL"))
    )
    (comp (ref "R29")
      (value "R_1/4WL")
      (footprint "eagle-import:R_1_4WL")
      (libsource (lib "eagle-import") (part "R_1/4WL"))
    )
    (comp (ref "R30")
      (value "R_RES_1206")
      (footprint "eagle-import:R_1206")
      (libsource (lib "eagle-import") (part "R_RES_1206"))
    )
    (comp (ref "R31")
      (value "R_RES_1206")
      (footprint "eagle-import:R_1206")
      (libsource (lib "eagle-import") (part "R_RES_1206"))
    )
    (comp (ref "ZAPDOS-20V")
      (value "PTN78020HAH")
      (footprint "eagle-import:R_PDSS-T7")
      (libsource (lib "eagle-import") (part "Q_PTN78020"))
    )
    (comp (ref "C48")
      (value "C_CAP_1206")
      (footprint "eagle-import:C_1206")
      (libsource (lib "eagle-import") (part "C_CAP_1206"))
    )
    (comp (ref "C49")
      (value "C_CAP_1206")
      (footprint "eagle-import:C_1206")
      (libsource (lib "eagle-import") (part "C_CAP_1206"))
    )
    (comp (ref "C50")
      (value "C_CAP_1206")
      (footprint "eagle-import:C_1206")
      (libsource (lib "eagle-import") (part "C_CAP_1206"))
    )
    (comp (ref "Q15")
      (value "U_FDPF045N10A_TO-220F")
      (footprint "eagle-import:TO220F")
      (libsource (lib "eagle-import") (part "U_FDPF045N10A_TO-220F"))
    )
    (comp (ref "R24")
      (value "R_RES_1206")
      (footprint "eagle-import:R_1206")
      (libsource (lib "eagle-import") (part "R_RES_1206"))
    )
    (comp (ref "U$70")
      (value "Q_MIC5021")
      (footprint "eagle-import:DIP8")
      (libsource (lib "eagle-import") (part "Q_MIC5021"))
    )
    (comp (ref "U$72")
      (value "J_1546074-2")
      (footprint "eagle-import:THERM_BLOCK_2")
      (libsource (lib "eagle-import") (part "J_1546074-2"))
    )
    (comp (ref "U$73")
      (value "R_2512")
      (footprint "eagle-import:R_2512")
      (libsource (lib "eagle-import") (part "R_2512"))
    )
    (comp (ref "C56")
      (value "C_POL8MM")
      (footprint "eagle-import:C_8MM")
      (libsource (lib "eagle-import") (part "C_POL8MM"))
    )
    (comp (ref "C57")
      (value "C_CAP_1206")
      (footprint "eagle-import:C_1206")
      (libsource (lib "eagle-import") (part "C_CAP_1206"))
    )
    (comp (ref "D8")
      (value "SB530-E3/54")
      (footprint "eagle-import:DIODE_D3.5MM_LS15.24MM")
      (libsource (lib "eagle-import") (part "D_1.5KE480A_D3.5MM_LS15.24MM"))
    )
    (comp (ref "D9")
      (value "SB530-E3/54")
      (footprint "eagle-import:DIODE_D3.5MM_LS15.24MM")
      (libsource (lib "eagle-import") (part "D_1.5KE480A_D3.5MM_LS15.24MM"))
    )
    (comp (ref "N1")
      (value "RJ45")
      (footprint "eagle-import:RJ45-CAT5E-2PACK")
      (libsource (lib "eagle-import") (part "RJ45-2PORT"))
    )
    (comp (ref "N2")
      (value "RJ45")
      (footprint "eagle-import:RJ45-CAT5E-2PACK")
      (libsource (lib "eagle-import") (part "RJ45-2PORT"))
    )
    (comp (ref "N3")
      (value "RJ45")
      (footprint "eagle-import:RJ45-CAT5E-2PACK")
      (libsource (lib "eagle-import") (part "RJ45-2PORT"))
    )
    (comp (ref "N4")
      (value "RJ45")
      (footprint "eagle-import:RJ45-CAT5E-2PACK")
      (libsource (lib "eagle-import") (part "RJ45-2PORT"))
    )
    (comp (ref "N5")
      (value "RJ45")
      (footprint "eagle-import:RJ45-CAT5E-2PACK")
      (libsource (lib "eagle-import") (part "RJ45-2PORT"))
    )
    (comp (ref "N6")
      (value "RJ45")
      (footprint "eagle-import:RJ45-CAT5E-2PACK")
      (libsource (lib "eagle-import") (part "RJ45-2PORT"))
    )
    (comp (ref "N7")
      (value "RJ45")
      (footprint "eagle-import:RJ45-CAT5E-2PACK")
      (libsource (lib "eagle-import") (part "RJ45-2PORT"))
    )
    (comp (ref "N8")
      (value "RJ45")
      (footprint "eagle-import:RJ45-CAT5E-2PACK")
      (libsource (lib "eagle-import") (part "RJ45-2PORT"))
    )
    (comp (ref "C5")
      (value "C_CAP_1206")
      (footprint "eagle-import:C_1206")
      (libsource (lib "eagle-import") (part "C_CAP_1206"))
    )
    (comp (ref "C6")
      (value "C_CAP_1206")
      (footprint "eagle-import:C_1206")
      (libsource (lib "eagle-import") (part "C_CAP_1206"))
    )
    (comp (ref "C11")
      (value "C_CAP_1206")
      (footprint "eagle-import:C_1206")
      (libsource (lib "eagle-import") (part "C_CAP_1206"))
    )
    (comp (ref "C12")
      (value "C_CAP_1206")
      (footprint "eagle-import:C_1206")
      (libsource (lib "eagle-import") (part "C_CAP_1206"))
    )
    (comp (ref "C13")
      (value "C_CAP_1206")
      (footprint "eagle-import:C_1206")
      (libsource (lib "eagle-import") (part "C_CAP_1206"))
    )
    (comp (ref "C16")
      (value "C_CAP_1206")
      (footprint "eagle-import:C_1206")
      (libsource (lib "eagle-import") (part "C_CAP_1206"))
    )
    (comp (ref "C51")
      (value "C_CAP_1206")
      (footprint "eagle-import:C_1206")
      (libsource (lib "eagle-import") (part "C_CAP_1206"))
    )
    (comp (ref "J1")
      (value "J_MC32857")
      (footprint "eagle-import:J_TOGGLE")
      (libsource (lib "eagle-import") (part "J_MC32857"))
    )
    (comp (ref "Q8")
      (value "Q_LDOHEATSINK")
      (footprint "eagle-import:TO220_6025DG")
      (libsource (lib "eagle-import") (part "Q_LDOHEATSINK"))
    )
    (comp (ref "Q9")
      (value "Q_LTC490")
      (footprint "eagle-import:DIP8")
      (libsource (lib "eagle-import") (part "Q_LTC490"))
    )
    (comp (ref "R1")
      (value "R_RES_1206")
      (footprint "eagle-import:R_1206")
      (libsource (lib "eagle-import") (part "R_RES_1206"))
    )
    (comp (ref "R6")
      (value "R_RES_1206")
      (footprint "eagle-import:R_1206")
      (libsource (lib "eagle-import") (part "R_RES_1206"))
    )
    (comp (ref "R8")
      (value "R_RES_1206")
      (footprint "eagle-import:R_1206")
      (libsource (lib "eagle-import") (part "R_RES_1206"))
    )
    (comp (ref "U$13")
      (value "Q_LM35TO-92")
      (footprint "eagle-import:TO-92-3")
      (libsource (lib "eagle-import") (part "Q_LM35TO-92"))
    )
    (comp (ref "U$57")
      (value "Q_ATMEGA328P")
      (footprint "eagle-import:DIP28")
      (libsource (lib "eagle-import") (part "Q_ATMEGA328P"))
    )
    (comp (ref "U$64")
      (value "RJ45")
      (footprint "eagle-import:RJ45-CAT5E")
      (libsource (lib "eagle-import") (part "RJ45"))
    )
    (comp (ref "X1")
      (value "HC49S")
      (footprint "eagle-import:HC-49")
      (libsource (lib "eagle-import") (part "X_HC49SCRYSTAL"))
    )
  )
  (nets
    (net (code "1") (name "+12V") (class "Default")
      (node (ref "C21") (pin "2") (pinfunction "2_2") (pintype "passive"))
      (node (ref "C75") (pin "1") (pinfunction "1_1") (pintype "passive"))
      (node (ref "P1") (pin "2") (pinfunction "+VIN_2") (pintype "input"))
      (node (ref "Q16") (pin "1") (pinfunction "VCC_1") (pintype "bidirectional"))
      (node (ref "Q18") (pin "3") (pinfunction "VOUT_3") (pintype "bidirectional"))
    )
    (net (code "2") (name "GND") (class "Default")
      (node (ref "C1") (pin "1") (pinfunction "1_1") (pintype "passive"))
      (node (ref "C10") (pin "1") (pinfunction "1_1") (pintype "passive"))
      (node (ref "C11") (pin "2") (pinfunction "2_2") (pintype "passive"))
      (node (ref "C12") (pin "1") (pinfunction "1_1") (pintype "passive"))
      (node (ref "C13") (pin "2") (pinfunction "2_2") (pintype "passive"))
      (node (ref "C14") (pin "-") (pinfunction "-_-") (pintype "passive"))
      (node (ref "C15") (pin "-") (pinfunction "-_-") (pintype "passive"))
      (node (ref "C16") (pin "2") (pinfunction "2_2") (pintype "passive"))
      (node (ref "C17") (pin "-") (pinfunction "-_-") (pintype "passive"))
      (node (ref "C18") (pin "2") (pinfunction "2_2") (pintype "passive"))
      (node (ref "C19") (pin "1") (pinfunction "1_1") (pintype "passive"))
      (node (ref "C2") (pin "1") (pinfunction "1_1") (pintype "passive"))
      (node (ref "C20") (pin "2") (pinfunction "2_2") (pintype "passive"))
      (node (ref "C21") (pin "1") (pinfunction "1_1") (pintype "passive"))
      (node (ref "C22") (pin "-") (pinfunction "-_-") (pintype "passive"))
      (node (ref "C23") (pin "2") (pinfunction "2_2") (pintype "passive"))
      (node (ref "C24") (pin "1") (pinfunction "1_1") (pintype "passive"))
      (node (ref "C25") (pin "2") (pinfunction "2_2") (pintype "passive"))
      (node (ref "C26") (pin "-") (pinfunction "-_-") (pintype "passive"))
      (node (ref "C27") (pin "2") (pinfunction "2_2") (pintype "passive"))
      (node (ref "C28") (pin "1") (pinfunction "1_1") (pintype "passive"))
      (node (ref "C29") (pin "1") (pinfunction "1_1") (pintype "passive"))
      (node (ref "C3") (pin "1") (pinfunction "1_1") (pintype "passive"))
      (node (ref "C36") (pin "2") (pinfunction "2_2") (pintype "passive"))
      (node (ref "C37") (pin "2") (pinfunction "2_2") (pintype "passive"))
      (node (ref "C38") (pin "2") (pinfunction "2_2") (pintype "passive"))
      (node (ref "C39") (pin "2") (pinfunction "2_2") (pintype "passive"))
      (node (ref "C4") (pin "1") (pinfunction "1_1") (pintype "passive"))
      (node (ref "C40") (pin "2") (pinfunction "2_2") (pintype "passive"))
      (node (ref "C41") (pin "2") (pinfunction "2_2") (pintype "passive"))
      (node (ref "C42") (pin "2") (pinfunction "2_2") (pintype "passive"))
      (node (ref "C43") (pin "2") (pinfunction "2_2") (pintype "passive"))
      (node (ref "C44") (pin "2") (pinfunction "2_2") (pintype "passive"))
      (node (ref "C45") (pin "2") (pinfunction "2_2") (pintype "passive"))
      (node (ref "C46") (pin "2") (pinfunction "2_2") (pintype "passive"))
      (node (ref "C47") (pin "2") (pinfunction "2_2") (pintype "passive"))
      (node (ref "C49") (pin "2") (pinfunction "2_2") (pintype "passive"))
      (node (ref "C5") (pin "1") (pinfunction "1_1") (pintype "passive"))
      (node (ref "C50") (pin "2") (pinfunction "2_2") (pintype "passive"))
      (node (ref "C51") (pin "1") (pinfunction "1_1") (pintype "passive"))
      (node (ref "C52") (pin "2") (pinfunction "2_2") (pintype "passive"))
      (node (ref "C53") (pin "2") (pinfunction "2_2") (pintype "passive"))
      (node (ref "C54") (pin "2") (pinfunction "2_2") (pintype "passive"))
      (node (ref "C55") (pin "2") (pinfunction "2_2") (pintype "passive"))
      (node (ref "C56") (pin "-") (pinfunction "-_-") (pintype "passive"))
      (node (ref "C57") (pin "2") (pinfunction "2_2") (pintype "passive"))
      (node (ref "C58") (pin "P$2") (pinfunction "-_P$2") (pintype "passive"))
      (node (ref "C59") (pin "P$2") (pinfunction "-_P$2") (pintype "passive"))
      (node (ref "C6") (pin "1") (pinfunction "1_1") (pintype "passive"))
      (node (ref "C60") (pin "P$2") (pinfunction "-_P$2") (pintype "passive"))
      (node (ref "C61") (pin "P$2") (pinfunction "-_P$2") (pintype "passive"))
      (node (ref "C62") (pin "P$2") (pinfunction "-_P$2") (pintype "passive"))
      (node (ref "C63") (pin "P$2") (pinfunction "-_P$2") (pintype "passive"))
      (node (ref "C64") (pin "P$2") (pinfunction "-_P$2") (pintype "passive"))
      (node (ref "C65") (pin "P$2") (pinfunction "-_P$2") (pintype "passive"))
      (node (ref "C66") (pin "P$2") (pinfunction "-_P$2") (pintype "passive"))
      (node (ref "C67") (pin "P$2") (pinfunction "-_P$2") (pintype "passive"))
      (node (ref "C68") (pin "2") (pinfunction "2_2") (pintype "passive"))
      (node (ref "C69") (pin "2") (pinfunction "2_2") (pintype "passive"))
      (node (ref "C7") (pin "2") (pinfunction "2_2") (pintype "passive"))
      (node (ref "C70") (pin "2") (pinfunction "2_2") (pintype "passive"))
      (node (ref "C71") (pin "2") (pinfunction "2_2") (pintype "passive"))
      (node (ref "C72") (pin "2") (pinfunction "2_2") (pintype "passive"))
      (node (ref "C73") (pin "2") (pinfunction "2_2") (pintype "passive"))
      (node (ref "C74") (pin "2") (pinfunction "2_2") (pintype "passive"))
      (node (ref "C75") (pin "2") (pinfunction "2_2") (pintype "passive"))
      (node (ref "C77") (pin "P$2") (pinfunction "-_P$2") (pintype "passive"))
      (node (ref "C78") (pin "P$2") (pinfunction "-_P$2") (pintype "passive"))
      (node (ref "C79") (pin "P$2") (pinfunction "-_P$2") (pintype "passive"))
      (node (ref "C8") (pin "2") (pinfunction "2_2") (pintype "passive"))
      (node (ref "C9") (pin "1") (pinfunction "1_1") (pintype "passive"))
      (node (ref "D1") (pin "A") (pinfunction "A_A") (pintype "passive"))
      (node (ref "D10") (pin "A") (pinfunction "A_A") (pintype "passive"))
      (node (ref "D2") (pin "A") (pinfunction "A_A") (pintype "passive"))
      (node (ref "D3") (pin "A") (pinfunction "A_A") (pintype "passive"))
      (node (ref "D4") (pin "A") (pinfunction "A_A") (pintype "passive"))
      (node (ref "D5") (pin "A") (pinfunction "A_A") (pintype "passive"))
      (node (ref "D6") (pin "A") (pinfunction "A_A") (pintype "passive"))
      (node (ref "D7") (pin "A") (pinfunction "A_A") (pintype "passive"))
      (node (ref "J1") (pin "P$1") (pinfunction "1_P$1") (pintype "bidirectional"))
      (node (ref "J2") (pin "PIN2-1") (pinfunction "2-1_PIN2-1") (pintype "bidirectional"))
      (node (ref "J2") (pin "PIN2-2") (pinfunction "2-2_PIN2-2") (pintype "bidirectional"))
      (node (ref "J3") (pin "P$2") (pinfunction "P$2_P$2") (pintype "bidirectional"))
      (node (ref "J4") (pin "P$2") (pinfunction "P$2_P$2") (pintype "bidirectional"))
      (node (ref "J5") (pin "P$2") (pinfunction "P$2_P$2") (pintype "bidirectional"))
      (node (ref "J6") (pin "P$2") (pinfunction "P$2_P$2") (pintype "bidirectional"))
      (node (ref "J7") (pin "P$2") (pinfunction "P$2_P$2") (pintype "bidirectional"))
      (node (ref "J8") (pin "P$2") (pinfunction "P$2_P$2") (pintype "bidirectional"))
      (node (ref "JOLTEON-12V-1") (pin "1") (pinfunction "GND_1") (pintype "bidirectional"))
      (node (ref "JOLTEON-12V-1") (pin "7") (pinfunction "GND1_7") (pintype "bidirectional"))
      (node (ref "MAGNEMITE-12V-2") (pin "1") (pinfunction "GND_1") (pintype "bidirectional"))
      (node (ref "MAGNEMITE-12V-2") (pin "7") (pinfunction "GND1_7") (pintype "bidirectional"))
      (node (ref "N1") (pin "1-7") (pinfunction "7-DC--_1-7") (pintype "bidirectional"))
      (node (ref "N1") (pin "1-8") (pinfunction "8-DC-_1-8") (pintype "bidirectional"))
      (node (ref "N1") (pin "2-7") (pinfunction "7-DC--_2-7") (pintype "bidirectional"))
      (node (ref "N1") (pin "2-8") (pinfunction "8-DC-_2-8") (pintype "bidirectional"))
      (node (ref "N2") (pin "1-7") (pinfunction "7-DC--_1-7") (pintype "bidirectional"))
      (node (ref "N2") (pin "1-8") (pinfunction "8-DC-_1-8") (pintype "bidirectional"))
      (node (ref "N2") (pin "2-7") (pinfunction "7-DC--_2-7") (pintype "bidirectional"))
      (node (ref "N2") (pin "2-8") (pinfunction "8-DC-_2-8") (pintype "bidirectional"))
      (node (ref "N3") (pin "1-7") (pinfunction "7-DC--_1-7") (pintype "bidirectional"))
      (node (ref "N3") (pin "1-8") (pinfunction "8-DC-_1-8") (pintype "bidirectional"))
      (node (ref "N3") (pin "2-7") (pinfunction "7-DC--_2-7") (pintype "bidirectional"))
      (node (ref "N3") (pin "2-8") (pinfunction "8-DC-_2-8") (pintype "bidirectional"))
      (node (ref "N4") (pin "1-7") (pinfunction "7-DC--_1-7") (pintype "bidirectional"))
      (node (ref "N4") (pin "1-8") (pinfunction "8-DC-_1-8") (pintype "bidirectional"))
      (node (ref "N4") (pin "2-7") (pinfunction "7-DC--_2-7") (pintype "bidirectional"))
      (node (ref "N4") (pin "2-8") (pinfunction "8-DC-_2-8") (pintype "bidirectional"))
      (node (ref "N5") (pin "1-7") (pinfunction "7-DC--_1-7") (pintype "bidirectional"))
      (node (ref "N5") (pin "1-8") (pinfunction "8-DC-_1-8") (pintype "bidirectional"))
      (node (ref "N5") (pin "2-7") (pinfunction "7-DC--_2-7") (pintype "bidirectional"))
      (node (ref "N5") (pin "2-8") (pinfunction "8-DC-_2-8") (pintype "bidirectional"))
      (node (ref "N6") (pin "1-7") (pinfunction "7-DC--_1-7") (pintype "bidirectional"))
      (node (ref "N6") (pin "1-8") (pinfunction "8-DC-_1-8") (pintype "bidirectional"))
      (node (ref "N6") (pin "2-7") (pinfunction "7-DC--_2-7") (pintype "bidirectional"))
      (node (ref "N6") (pin "2-8") (pinfunction "8-DC-_2-8") (pintype "bidirectional"))
      (node (ref "N7") (pin "1-7") (pinfunction "7-DC--_1-7") (pintype "bidirectional"))
      (node (ref "N7") (pin "1-8") (pinfunction "8-DC-_1-8") (pintype "bidirectional"))
      (node (ref "N7") (pin "2-7") (pinfunction "7-DC--_2-7") (pintype "bidirectional"))
      (node (ref "N7") (pin "2-8") (pinfunction "8-DC-_2-8") (pintype "bidirectional"))
      (node (ref "N8") (pin "1-7") (pinfunction "7-DC--_1-7") (pintype "bidirectional"))
      (node (ref "N8") (pin "1-8") (pinfunction "8-DC-_1-8") (pintype "bidirectional"))
      (node (ref "N8") (pin "2-7") (pinfunction "7-DC--_2-7") (pintype "bidirectional"))
      (node (ref "N8") (pin "2-8") (pinfunction "8-DC-_2-8") (pintype "bidirectional"))
      (node (ref "P1") (pin "1") (pinfunction "-VIN_1") (pintype "input"))
      (node (ref "PICKACHU-5V") (pin "1") (pinfunction "GND_1") (pintype "bidirectional"))
      (node (ref "PICKACHU-5V") (pin "7") (pinfunction "GND1_7") (pintype "bidirectional"))
      (node (ref "Q10") (pin "1") (pinfunction "S_1") (pintype "bidirectional"))
      (node (ref "Q11") (pin "1") (pinfunction "S_1") (pintype "bidirectional"))
      (node (ref "Q12") (pin "1") (pinfunction "S_1") (pintype "bidirectional"))
      (node (ref "Q14") (pin "1") (pinfunction "S_1") (pintype "bidirectional"))
      (node (ref "Q16") (pin "4") (pinfunction "GND_4") (pintype "bidirectional"))
      (node (ref "Q17") (pin "2") (pinfunction "GND_2") (pintype "bidirectional"))
      (node (ref "Q17") (pin "7") (pinfunction "REF1_7") (pintype "bidirectional"))
      (node (ref "Q18") (pin "2") (pinfunction "GND_2") (pintype "bidirectional"))
      (node (ref "Q8") (pin "2") (pinfunction "GND_2") (pintype "bidirectional"))
      (node (ref "Q9") (pin "4") (pinfunction "GND_4") (pintype "bidirectional"))
      (node (ref "R10") (pin "1") (pinfunction "1_1") (pintype "passive"))
      (node (ref "R12") (pin "1") (pinfunction "1_1") (pintype "passive"))
      (node (ref "R2") (pin "1") (pinfunction "1_1") (pintype "passive"))
      (node (ref "R28") (pin "1") (pinfunction "1_1") (pintype "passive"))
      (node (ref "R3") (pin "1") (pinfunction "1_1") (pintype "passive"))
      (node (ref "R30") (pin "1") (pinfunction "1_1") (pintype "passive"))
      (node (ref "R31") (pin "1") (pinfunction "1_1") (pintype "passive"))
      (node (ref "R4") (pin "1") (pinfunction "1_1") (pintype "passive"))
      (node (ref "R5") (pin "1") (pinfunction "1_1") (pintype "passive"))
      (node (ref "RAICHU-5V-CRIT") (pin "1") (pinfunction "GND_1") (pintype "bidirectional"))
      (node (ref "RAICHU-5V-CRIT") (pin "7") (pinfunction "GND1_7") (pintype "bidirectional"))
      (node (ref "U$11") (pin "4") (pinfunction "GND_4") (pintype "bidirectional"))
      (node (ref "U$13") (pin "3") (pinfunction "GND_3") (pintype "bidirectional"))
      (node (ref "U$14") (pin "P$2") (pinfunction "P$2_P$2") (pintype "bidirectional"))
      (node (ref "U$23") (pin "4") (pinfunction "GND_4") (pintype "bidirectional"))
      (node (ref "U$26") (pin "P$2") (pinfunction "P$2_P$2") (pintype "bidirectional"))
      (node (ref "U$27") (pin "4") (pinfunction "GND_4") (pintype "bidirectional"))
      (node (ref "U$31") (pin "P$2") (pinfunction "P$2_P$2") (pintype "bidirectional"))
      (node (ref "U$32") (pin "4") (pinfunction "GND_4") (pintype "bidirectional"))
      (node (ref "U$36") (pin "P$2") (pinfunction "P$2_P$2") (pintype "bidirectional"))
      (node (ref "U$37") (pin "4") (pinfunction "GND_4") (pintype "bidirectional"))
      (node (ref "U$40") (pin "P$2") (pinfunction "P$2_P$2") (pintype "bidirectional"))
      (node (ref "U$41") (pin "4") (pinfunction "GND_4") (pintype "bidirectional"))
      (node (ref "U$44") (pin "P$2") (pinfunction "P$2_P$2") (pintype "bidirectional"))
      (node (ref "U$52") (pin "P$2") (pinfunction "P$2_P$2") (pintype "bidirectional"))
      (node (ref "U$53") (pin "P$2") (pinfunction "P$2_P$2") (pintype "bidirectional"))
      (node (ref "U$54") (pin "P$2") (pinfunction "P$2_P$2") (pintype "bidirectional"))
      (node (ref "U$55") (pin "P$2") (pinfunction "P$2_P$2") (pintype "bidirectional"))
      (node (ref "U$57") (pin "22") (pinfunction "GND1_22") (pintype "bidirectional"))
      (node (ref "U$57") (pin "8") (pinfunction "GND_8") (pintype "bidirectional"))
      (node (ref "U$64") (pin "7") (pinfunction "7-DC--_7") (pintype "bidirectional"))
      (node (ref "U$64") (pin "8") (pinfunction "8-DC-_8") (pintype "bidirectional"))
      (node (ref "U$70") (pin "4") (pinfunction "GND_4") (pintype "bidirectional"))
      (node (ref "U$72") (pin "P$2") (pinfunction "P$2_P$2") (pintype "bidirectional"))
      (node (ref "ZAPDOS-20V") (pin "1") (pinfunction "GND_1") (pintype "bidirectional"))
      (node (ref "ZAPDOS-20V") (pin "7") (pinfunction "GND1_7") (pintype "bidirectional"))
    )
    (net (code "3") (name "HIGHSIDE") (class "Default")
      (node (ref "C76") (pin "1") (pinfunction "1_1") (pintype "passive"))
      (node (ref "P1") (pin "4") (pinfunction "+VO_4") (pintype "output"))
      (node (ref "Q16") (pin "8") (pinfunction "VB_8") (pintype "bidirectional"))
    )
    (net (code "4") (name "IN+") (class "Default")
      (node (ref "Q17") (pin "1") (pinfunction "-IN_1") (pintype "bidirectional"))
      (node (ref "R7") (pin "SENSE1") (pinfunction "SENSE1_SENSE1") (pintype "bidirectional"))
    )
    (net (code "5") (name "IN-") (class "Default")
      (node (ref "Q17") (pin "8") (pinfunction "+IN_8") (pintype "bidirectional"))
      (node (ref "R7") (pin "SENSE2") (pinfunction "SENSE2_SENSE2") (pintype "bidirectional"))
    )
    (net (code "6") (name "MAINGATE") (class "Default")
      (node (ref "Q13") (pin "1") (pinfunction "G_1") (pintype "bidirectional"))
      (node (ref "Q2") (pin "1") (pinfunction "G_1") (pintype "bidirectional"))
      (node (ref "R32") (pin "1") (pinfunction "1_1") (pintype "passive"))
    )
    (net (code "7") (name "M_IMAIN") (class "Default")
      (node (ref "Q17") (pin "5") (pinfunction "OUT_5") (pintype "bidirectional"))
      (node (ref "U$57") (pin "28") (pinfunction "PC5_28") (pintype "bidirectional"))
    )
    (net (code "8") (name "M_V5-2") (class "Default")
      (node (ref "C52") (pin "1") (pinfunction "1_1") (pintype "passive"))
      (node (ref "R26") (pin "1") (pinfunction "1_1") (pintype "passive"))
      (node (ref "R28") (pin "2") (pinfunction "2_2") (pintype "passive"))
      (node (ref "U$57") (pin "24") (pinfunction "PC1_24") (pintype "bidirectional"))
    )
    (net (code "9") (name "M_V12-1") (class "Default")
      (node (ref "C53") (pin "1") (pinfunction "1_1") (pintype "passive"))
      (node (ref "R27") (pin "1") (pinfunction "1_1") (pintype "passive"))
      (node (ref "R30") (pin "2") (pinfunction "2_2") (pintype "passive"))
      (node (ref "U$57") (pin "25") (pinfunction "PC2_25") (pintype "bidirectional"))
    )
    (net (code "10") (name "M_V12-2") (class "Default")
      (node (ref "C54") (pin "1") (pinfunction "1_1") (pintype "passive"))
      (node (ref "R29") (pin "1") (pinfunction "1_1") (pintype "passive"))
      (node (ref "R31") (pin "2") (pinfunction "2_2") (pintype "passive"))
      (node (ref "U$57") (pin "26") (pinfunction "PC3_26") (pintype "bidirectional"))
    )
    (net (code "11") (name "M_VMAIN") (class "Default")
      (node (ref "C25") (pin "1") (pinfunction "1_1") (pintype "passive"))
      (node (ref "R10") (pin "2") (pinfunction "2_2") (pintype "passive"))
      (node (ref "R25") (pin "2") (pinfunction "2_2") (pintype "passive"))
      (node (ref "U$57") (pin "27") (pinfunction "PC4_27") (pintype "bidirectional"))
    )
    (net (code "12") (name "N$45") (class "Default")
      (node (ref "C76") (pin "2") (pinfunction "2_2") (pintype "passive"))
      (node (ref "P1") (pin "3") (pinfunction "-VO_3") (pintype "output"))
      (node (ref "Q13") (pin "3") (pinfunction "S_3") (pintype "bidirectional"))
      (node (ref "Q16") (pin "6") (pinfunction "VS_6") (pintype "bidirectional"))
      (node (ref "Q2") (pin "3") (pinfunction "S_3") (pintype "bidirectional"))
      (node (ref "R7") (pin "1") (pinfunction "1_1") (pintype "passive"))
    )
    (net (code "13") (name "Net-(D1-K)") (class "Default")
      (node (ref "C18") (pin "1") (pinfunction "1_1") (pintype "passive"))
      (node (ref "C73") (pin "1") (pinfunction "1_1") (pintype "passive"))
      (node (ref "D1") (pin "C") (pinfunction "K_C") (pintype "passive"))
      (node (ref "J6") (pin "P$1") (pinfunction "P$1_P$1") (pintype "bidirectional"))
      (node (ref "J7") (pin "P$1") (pinfunction "P$1_P$1") (pintype "bidirectional"))
      (node (ref "J8") (pin "P$1") (pinfunction "P$1_P$1") (pintype "bidirectional"))
      (node (ref "L6") (pin "5") (pinfunction "5_5") (pintype "bidirectional"))
      (node (ref "L6") (pin "6") (pinfunction "6_6") (pintype "bidirectional"))
      (node (ref "L6") (pin "7") (pinfunction "7_7") (pintype "bidirectional"))
      (node (ref "L6") (pin "8") (pinfunction "8_8") (pintype "bidirectional"))
    )
    (net (code "14") (name "Net-(D2-K)") (class "Default")
      (node (ref "C23") (pin "1") (pinfunction "1_1") (pintype "passive"))
      (node (ref "C74") (pin "1") (pinfunction "1_1") (pintype "passive"))
      (node (ref "D2") (pin "C") (pinfunction "K_C") (pintype "passive"))
      (node (ref "J3") (pin "P$1") (pinfunction "P$1_P$1") (pintype "bidirectional"))
      (node (ref "J4") (pin "P$1") (pinfunction "P$1_P$1") (pintype "bidirectional"))
      (node (ref "J5") (pin "P$1") (pinfunction "P$1_P$1") (pintype "bidirectional"))
      (node (ref "L8") (pin "5") (pinfunction "5_5") (pintype "bidirectional"))
      (node (ref "L8") (pin "6") (pinfunction "6_6") (pintype "bidirectional"))
      (node (ref "L8") (pin "7") (pinfunction "7_7") (pintype "bidirectional"))
      (node (ref "L8") (pin "8") (pinfunction "8_8") (pintype "bidirectional"))
    )
    (net (code "15") (name "Net-(D3-K)") (class "Default")
      (node (ref "C72") (pin "1") (pinfunction "1_1") (pintype "passive"))
      (node (ref "C8") (pin "1") (pinfunction "1_1") (pintype "passive"))
      (node (ref "D3") (pin "C") (pinfunction "K_C") (pintype "passive"))
      (node (ref "L4") (pin "5") (pinfunction "5_5") (pintype "bidirectional"))
      (node (ref "L4") (pin "6") (pinfunction "6_6") (pintype "bidirectional"))
      (node (ref "L4") (pin "7") (pinfunction "7_7") (pintype "bidirectional"))
      (node (ref "L4") (pin "8") (pinfunction "8_8") (pintype "bidirectional"))
      (node (ref "U$52") (pin "P$1") (pinfunction "P$1_P$1") (pintype "bidirectional"))
      (node (ref "U$53") (pin "P$1") (pinfunction "P$1_P$1") (pintype "bidirectional"))
    )
    (net (code "16") (name "Net-(D7-K)") (class "Default")
      (node (ref "C7") (pin "1") (pinfunction "1_1") (pintype "passive"))
      (node (ref "C71") (pin "1") (pinfunction "1_1") (pintype "passive"))
      (node (ref "D7") (pin "C") (pinfunction "K_C") (pintype "passive"))
      (node (ref "L3") (pin "5") (pinfunction "5_5") (pintype "bidirectional"))
      (node (ref "L3") (pin "6") (pinfunction "6_6") (pintype "bidirectional"))
      (node (ref "L3") (pin "7") (pinfunction "7_7") (pintype "bidirectional"))
      (node (ref "L3") (pin "8") (pinfunction "8_8") (pintype "bidirectional"))
      (node (ref "U$54") (pin "P$1") (pinfunction "P$1_P$1") (pintype "bidirectional"))
      (node (ref "U$55") (pin "P$1") (pinfunction "P$1_P$1") (pintype "bidirectional"))
    )
    (net (code "17") (name "Net-(J1-2)") (class "Default")
      (node (ref "J1") (pin "P$2") (pinfunction "2_P$2") (pintype "bidirectional"))
      (node (ref "R1") (pin "1") (pinfunction "1_1") (pintype "passive"))
      (node (ref "U$57") (pin "1") (pinfunction "PC6_1") (pintype "bidirectional"))
    )
    (net (code "18") (name "Net-(JOLTEON-12V-1-ADJUST)") (class "Default")
      (node (ref "JOLTEON-12V-1") (pin "4") (pinfunction "ADJUST_4") (pintype "bidirectional"))
      (node (ref "R5") (pin "2") (pinfunction "2_2") (pintype "passive"))
    )
    (net (code "19") (name "Net-(JOLTEON-12V-1-INHIBIT)") (class "Default")
      (node (ref "JOLTEON-12V-1") (pin "3") (pinfunction "INHIBIT_3") (pintype "bidirectional"))
      (node (ref "Q10") (pin "3") (pinfunction "D_3") (pintype "bidirectional"))
    )
    (net (code "20") (name "Net-(JOLTEON-12V-1-SENSE)") (class "Default")
      (node (ref "C22") (pin "+") (pinfunction "+_+") (pintype "passive"))
      (node (ref "JOLTEON-12V-1") (pin "5") (pinfunction "SENSE_5") (pintype "bidirectional"))
      (node (ref "JOLTEON-12V-1") (pin "6") (pinfunction "VOUT_6") (pintype "bidirectional"))
      (node (ref "L8") (pin "1") (pinfunction "1_1") (pintype "bidirectional"))
      (node (ref "L8") (pin "2") (pinfunction "2_2") (pintype "bidirectional"))
      (node (ref "L8") (pin "3") (pinfunction "3_3") (pintype "bidirectional"))
      (node (ref "L8") (pin "4") (pinfunction "4_4") (pintype "bidirectional"))
      (node (ref "R27") (pin "2") (pinfunction "2_2") (pintype "passive"))
    )
    (net (code "21") (name "Net-(JOLTEON-12V-1-VIN)") (class "Default")
      (node (ref "C2") (pin "2") (pinfunction "2_2") (pintype "passive"))
      (node (ref "JOLTEON-12V-1") (pin "2") (pinfunction "VIN_2") (pintype "bidirectional"))
      (node (ref "L7") (pin "5") (pinfunction "5_5") (pintype "bidirectional"))
      (node (ref "L7") (pin "6") (pinfunction "6_6") (pintype "bidirectional"))
      (node (ref "L7") (pin "7") (pinfunction "7_7") (pintype "bidirectional"))
      (node (ref "L7") (pin "8") (pinfunction "8_8") (pintype "bidirectional"))
    )
    (net (code "22") (name "Net-(MAGNEMITE-12V-2-ADJUST)") (class "Default")
      (node (ref "MAGNEMITE-12V-2") (pin "4") (pinfunction "ADJUST_4") (pintype "bidirectional"))
      (node (ref "R4") (pin "2") (pinfunction "2_2") (pintype "passive"))
    )
    (net (code "23") (name "Net-(MAGNEMITE-12V-2-INHIBIT)") (class "Default")
      (node (ref "MAGNEMITE-12V-2") (pin "3") (pinfunction "INHIBIT_3") (pintype "bidirectional"))
      (node (ref "Q12") (pin "3") (pinfunction "D_3") (pintype "bidirectional"))
    )
    (net (code "24") (name "Net-(MAGNEMITE-12V-2-SENSE)") (class "Default")
      (node (ref "C26") (pin "+") (pinfunction "+_+") (pintype "passive"))
      (node (ref "L6") (pin "1") (pinfunction "1_1") (pintype "bidirectional"))
      (node (ref "L6") (pin "2") (pinfunction "2_2") (pintype "bidirectional"))
      (node (ref "L6") (pin "3") (pinfunction "3_3") (pintype "bidirectional"))
      (node (ref "L6") (pin "4") (pinfunction "4_4") (pintype "bidirectional"))
      (node (ref "MAGNEMITE-12V-2") (pin "5") (pinfunction "SENSE_5") (pintype "bidirectional"))
      (node (ref "MAGNEMITE-12V-2") (pin "6") (pinfunction "VOUT_6") (pintype "bidirectional"))
      (node (ref "R29") (pin "2") (pinfunction "2_2") (pintype "passive"))
    )
    (net (code "25") (name "Net-(MAGNEMITE-12V-2-VIN)") (class "Default")
      (node (ref "C1") (pin "2") (pinfunction "2_2") (pintype "passive"))
      (node (ref "L5") (pin "5") (pinfunction "5_5") (pintype "bidirectional"))
      (node (ref "L5") (pin "6") (pinfunction "6_6") (pintype "bidirectional"))
      (node (ref "L5") (pin "7") (pinfunction "7_7") (pintype "bidirectional"))
      (node (ref "L5") (pin "8") (pinfunction "8_8") (pintype "bidirectional"))
      (node (ref "MAGNEMITE-12V-2") (pin "2") (pinfunction "VIN_2") (pintype "bidirectional"))
    )
    (net (code "26") (name "Net-(N1A-1-TRANS+)") (class "Default")
      (node (ref "N1") (pin "1-1") (pinfunction "1-TRANS+_1-1") (pintype "bidirectional"))
      (node (ref "N1") (pin "2-1") (pinfunction "1-TRANS+_2-1") (pintype "bidirectional"))
    )
    (net (code "27") (name "Net-(N1A-2-TRANS-)") (class "Default")
      (node (ref "N1") (pin "1-2") (pinfunction "2-TRANS-_1-2") (pintype "bidirectional"))
      (node (ref "N1") (pin "2-2") (pinfunction "2-TRANS-_2-2") (pintype "bidirectional"))
    )
    (net (code "28") (name "Net-(N1A-3+RECEIVE+)") (class "Default")
      (node (ref "N1") (pin "1-3") (pinfunction "3+RECEIVE+_1-3") (pintype "bidirectional"))
      (node (ref "N1") (pin "2-3") (pinfunction "3+RECEIVE+_2-3") (pintype "bidirectional"))
    )
    (net (code "29") (name "Net-(N1A-6-RECEIVE-)") (class "Default")
      (node (ref "N1") (pin "1-6") (pinfunction "6-RECEIVE-_1-6") (pintype "bidirectional"))
      (node (ref "N1") (pin "2-6") (pinfunction "6-RECEIVE-_2-6") (pintype "bidirectional"))
    )
    (net (code "30") (name "Net-(N2A-1-TRANS+)") (class "Default")
      (node (ref "N2") (pin "1-1") (pinfunction "1-TRANS+_1-1") (pintype "bidirectional"))
      (node (ref "N2") (pin "2-1") (pinfunction "1-TRANS+_2-1") (pintype "bidirectional"))
    )
    (net (code "31") (name "Net-(N2A-2-TRANS-)") (class "Default")
      (node (ref "N2") (pin "1-2") (pinfunction "2-TRANS-_1-2") (pintype "bidirectional"))
      (node (ref "N2") (pin "2-2") (pinfunction "2-TRANS-_2-2") (pintype "bidirectional"))
    )
    (net (code "32") (name "Net-(N2A-3+RECEIVE+)") (class "Default")
      (node (ref "N2") (pin "1-3") (pinfunction "3+RECEIVE+_1-3") (pintype "bidirectional"))
      (node (ref "N2") (pin "2-3") (pinfunction "3+RECEIVE+_2-3") (pintype "bidirectional"))
    )
    (net (code "33") (name "Net-(N2A-6-RECEIVE-)") (class "Default")
      (node (ref "N2") (pin "1-6") (pinfunction "6-RECEIVE-_1-6") (pintype "bidirectional"))
      (node (ref "N2") (pin "2-6") (pinfunction "6-RECEIVE-_2-6") (pintype "bidirectional"))
    )
    (net (code "34") (name "Net-(N3A-1-TRANS+)") (class "Default")
      (node (ref "N3") (pin "1-1") (pinfunction "1-TRANS+_1-1") (pintype "bidirectional"))
      (node (ref "N3") (pin "2-1") (pinfunction "1-TRANS+_2-1") (pintype "bidirectional"))
    )
    (net (code "35") (name "Net-(N3A-2-TRANS-)") (class "Default")
      (node (ref "N3") (pin "1-2") (pinfunction "2-TRANS-_1-2") (pintype "bidirectional"))
      (node (ref "N3") (pin "2-2") (pinfunction "2-TRANS-_2-2") (pintype "bidirectional"))
    )
    (net (code "36") (name "Net-(N3A-3+RECEIVE+)") (class "Default")
      (node (ref "N3") (pin "1-3") (pinfunction "3+RECEIVE+_1-3") (pintype "bidirectional"))
      (node (ref "N3") (pin "2-3") (pinfunction "3+RECEIVE+_2-3") (pintype "bidirectional"))
    )
    (net (code "37") (name "Net-(N3A-6-RECEIVE-)") (class "Default")
      (node (ref "N3") (pin "1-6") (pinfunction "6-RECEIVE-_1-6") (pintype "bidirectional"))
      (node (ref "N3") (pin "2-6") (pinfunction "6-RECEIVE-_2-6") (pintype "bidirectional"))
    )
    (net (code "38") (name "Net-(N4A-1-TRANS+)") (class "Default")
      (node (ref "N4") (pin "1-1") (pinfunction "1-TRANS+_1-1") (pintype "bidirectional"))
      (node (ref "N4") (pin "2-1") (pinfunction "1-TRANS+_2-1") (pintype "bidirectional"))
    )
    (net (code "39") (name "Net-(N4A-2-TRANS-)") (class "Default")
      (node (ref "N4") (pin "1-2") (pinfunction "2-TRANS-_1-2") (pintype "bidirectional"))
      (node (ref "N4") (pin "2-2") (pinfunction "2-TRANS-_2-2") (pintype "bidirectional"))
    )
    (net (code "40") (name "Net-(N4A-3+RECEIVE+)") (class "Default")
      (node (ref "N4") (pin "1-3") (pinfunction "3+RECEIVE+_1-3") (pintype "bidirectional"))
      (node (ref "N4") (pin "2-3") (pinfunction "3+RECEIVE+_2-3") (pintype "bidirectional"))
    )
    (net (code "41") (name "Net-(N4A-6-RECEIVE-)") (class "Default")
      (node (ref "N4") (pin "1-6") (pinfunction "6-RECEIVE-_1-6") (pintype "bidirectional"))
      (node (ref "N4") (pin "2-6") (pinfunction "6-RECEIVE-_2-6") (pintype "bidirectional"))
    )
    (net (code "42") (name "Net-(N5A-1-TRANS+)") (class "Default")
      (node (ref "N5") (pin "1-1") (pinfunction "1-TRANS+_1-1") (pintype "bidirectional"))
      (node (ref "N5") (pin "2-1") (pinfunction "1-TRANS+_2-1") (pintype "bidirectional"))
    )
    (net (code "43") (name "Net-(N5A-2-TRANS-)") (class "Default")
      (node (ref "N5") (pin "1-2") (pinfunction "2-TRANS-_1-2") (pintype "bidirectional"))
      (node (ref "N5") (pin "2-2") (pinfunction "2-TRANS-_2-2") (pintype "bidirectional"))
    )
    (net (code "44") (name "Net-(N5A-3+RECEIVE+)") (class "Default")
      (node (ref "N5") (pin "1-3") (pinfunction "3+RECEIVE+_1-3") (pintype "bidirectional"))
      (node (ref "N5") (pin "2-3") (pinfunction "3+RECEIVE+_2-3") (pintype "bidirectional"))
    )
    (net (code "45") (name "Net-(N5A-6-RECEIVE-)") (class "Default")
      (node (ref "N5") (pin "1-6") (pinfunction "6-RECEIVE-_1-6") (pintype "bidirectional"))
      (node (ref "N5") (pin "2-6") (pinfunction "6-RECEIVE-_2-6") (pintype "bidirectional"))
    )
    (net (code "46") (name "Net-(N6A-1-TRANS+)") (class "Default")
      (node (ref "N6") (pin "1-1") (pinfunction "1-TRANS+_1-1") (pintype "bidirectional"))
      (node (ref "N6") (pin "2-1") (pinfunction "1-TRANS+_2-1") (pintype "bidirectional"))
    )
    (net (code "47") (name "Net-(N6A-2-TRANS-)") (class "Default")
      (node (ref "N6") (pin "1-2") (pinfunction "2-TRANS-_1-2") (pintype "bidirectional"))
      (node (ref "N6") (pin "2-2") (pinfunction "2-TRANS-_2-2") (pintype "bidirectional"))
    )
    (net (code "48") (name "Net-(N6A-3+RECEIVE+)") (class "Default")
      (node (ref "N6") (pin "1-3") (pinfunction "3+RECEIVE+_1-3") (pintype "bidirectional"))
      (node (ref "N6") (pin "2-3") (pinfunction "3+RECEIVE+_2-3") (pintype "bidirectional"))
    )
    (net (code "49") (name "Net-(N6A-6-RECEIVE-)") (class "Default")
      (node (ref "N6") (pin "1-6") (pinfunction "6-RECEIVE-_1-6") (pintype "bidirectional"))
      (node (ref "N6") (pin "2-6") (pinfunction "6-RECEIVE-_2-6") (pintype "bidirectional"))
    )
    (net (code "50") (name "Net-(N7A-1-TRANS+)") (class "Default")
      (node (ref "N7") (pin "1-1") (pinfunction "1-TRANS+_1-1") (pintype "bidirectional"))
      (node (ref "N7") (pin "2-1") (pinfunction "1-TRANS+_2-1") (pintype "bidirectional"))
    )
    (net (code "51") (name "Net-(N7A-2-TRANS-)") (class "Default")
      (node (ref "N7") (pin "1-2") (pinfunction "2-TRANS-_1-2") (pintype "bidirectional"))
      (node (ref "N7") (pin "2-2") (pinfunction "2-TRANS-_2-2") (pintype "bidirectional"))
    )
    (net (code "52") (name "Net-(N7A-3+RECEIVE+)") (class "Default")
      (node (ref "N7") (pin "1-3") (pinfunction "3+RECEIVE+_1-3") (pintype "bidirectional"))
      (node (ref "N7") (pin "2-3") (pinfunction "3+RECEIVE+_2-3") (pintype "bidirectional"))
    )
    (net (code "53") (name "Net-(N7A-6-RECEIVE-)") (class "Default")
      (node (ref "N7") (pin "1-6") (pinfunction "6-RECEIVE-_1-6") (pintype "bidirectional"))
      (node (ref "N7") (pin "2-6") (pinfunction "6-RECEIVE-_2-6") (pintype "bidirectional"))
    )
    (net (code "54") (name "Net-(N8A-1-TRANS+)") (class "Default")
      (node (ref "N8") (pin "1-1") (pinfunction "1-TRANS+_1-1") (pintype "bidirectional"))
      (node (ref "N8") (pin "2-1") (pinfunction "1-TRANS+_2-1") (pintype "bidirectional"))
    )
    (net (code "55") (name "Net-(N8A-2-TRANS-)") (class "Default")
      (node (ref "N8") (pin "1-2") (pinfunction "2-TRANS-_1-2") (pintype "bidirectional"))
      (node (ref "N8") (pin "2-2") (pinfunction "2-TRANS-_2-2") (pintype "bidirectional"))
    )
    (net (code "56") (name "Net-(N8A-3+RECEIVE+)") (class "Default")
      (node (ref "N8") (pin "1-3") (pinfunction "3+RECEIVE+_1-3") (pintype "bidirectional"))
      (node (ref "N8") (pin "2-3") (pinfunction "3+RECEIVE+_2-3") (pintype "bidirectional"))
    )
    (net (code "57") (name "Net-(N8A-6-RECEIVE-)") (class "Default")
      (node (ref "N8") (pin "1-6") (pinfunction "6-RECEIVE-_1-6") (pintype "bidirectional"))
      (node (ref "N8") (pin "2-6") (pinfunction "6-RECEIVE-_2-6") (pintype "bidirectional"))
    )
    (net (code "58") (name "Net-(PICKACHU-5V-ADJUST)") (class "Default")
      (node (ref "PICKACHU-5V") (pin "4") (pinfunction "ADJUST_4") (pintype "bidirectional"))
      (node (ref "R2") (pin "2") (pinfunction "2_2") (pintype "passive"))
    )
    (net (code "59") (name "Net-(PICKACHU-5V-INHIBIT)") (class "Default")
      (node (ref "PICKACHU-5V") (pin "3") (pinfunction "INHIBIT_3") (pintype "bidirectional"))
      (node (ref "Q14") (pin "3") (pinfunction "D_3") (pintype "bidirectional"))
    )
    (net (code "60") (name "Net-(PICKACHU-5V-SENSE)") (class "Default")
      (node (ref "C14") (pin "+") (pinfunction "+_+") (pintype "passive"))
      (node (ref "L3") (pin "1") (pinfunction "1_1") (pintype "bidirectional"))
      (node (ref "L3") (pin "2") (pinfunction "2_2") (pintype "bidirectional"))
      (node (ref "L3") (pin "3") (pinfunction "3_3") (pintype "bidirectional"))
      (node (ref "L3") (pin "4") (pinfunction "4_4") (pintype "bidirectional"))
      (node (ref "PICKACHU-5V") (pin "5") (pinfunction "SENSE_5") (pintype "bidirectional"))
      (node (ref "PICKACHU-5V") (pin "6") (pinfunction "VOUT_6") (pintype "bidirectional"))
      (node (ref "R26") (pin "2") (pinfunction "2_2") (pintype "passive"))
    )
    (net (code "61") (name "Net-(PICKACHU-5V-VIN)") (class "Default")
      (node (ref "C3") (pin "2") (pinfunction "2_2") (pintype "passive"))
      (node (ref "L2") (pin "5") (pinfunction "5_5") (pintype "bidirectional"))
      (node (ref "L2") (pin "6") (pinfunction "6_6") (pintype "bidirectional"))
      (node (ref "L2") (pin "7") (pinfunction "7_7") (pintype "bidirectional"))
      (node (ref "L2") (pin "8") (pinfunction "8_8") (pintype "bidirectional"))
      (node (ref "PICKACHU-5V") (pin "2") (pinfunction "VIN_2") (pintype "bidirectional"))
    )
    (net (code "62") (name "Net-(Q1-G)") (class "Default")
      (node (ref "Q1") (pin "1") (pinfunction "G_1") (pintype "passive"))
      (node (ref "U$11") (pin "7") (pinfunction "GATE_7") (pintype "bidirectional"))
    )
    (net (code "63") (name "Net-(Q1-S)") (class "Default")
      (node (ref "Q1") (pin "3") (pinfunction "S_3") (pintype "passive"))
      (node (ref "U$11") (pin "5") (pinfunction "SENSE+_5") (pintype "bidirectional"))
      (node (ref "U$49") (pin "P$2") (pinfunction "2_P$2") (pintype "passive"))
    )
    (net (code "64") (name "Net-(Q3-G)") (class "Default")
      (node (ref "Q3") (pin "1") (pinfunction "G_1") (pintype "passive"))
      (node (ref "U$23") (pin "7") (pinfunction "GATE_7") (pintype "bidirectional"))
    )
    (net (code "65") (name "Net-(Q3-S)") (class "Default")
      (node (ref "Q3") (pin "3") (pinfunction "S_3") (pintype "passive"))
      (node (ref "U$23") (pin "5") (pinfunction "SENSE+_5") (pintype "bidirectional"))
      (node (ref "U$50") (pin "P$2") (pinfunction "2_P$2") (pintype "passive"))
    )
    (net (code "66") (name "Net-(Q4-G)") (class "Default")
      (node (ref "Q4") (pin "1") (pinfunction "G_1") (pintype "passive"))
      (node (ref "U$27") (pin "7") (pinfunction "GATE_7") (pintype "bidirectional"))
    )
    (net (code "67") (name "Net-(Q4-S)") (class "Default")
      (node (ref "Q4") (pin "3") (pinfunction "S_3") (pintype "passive"))
      (node (ref "U$27") (pin "5") (pinfunction "SENSE+_5") (pintype "bidirectional"))
      (node (ref "U$48") (pin "P$2") (pinfunction "2_P$2") (pintype "passive"))
    )
    (net (code "68") (name "Net-(Q5-G)") (class "Default")
      (node (ref "Q5") (pin "1") (pinfunction "G_1") (pintype "passive"))
      (node (ref "U$32") (pin "7") (pinfunction "GATE_7") (pintype "bidirectional"))
    )
    (net (code "69") (name "Net-(Q5-S)") (class "Default")
      (node (ref "Q5") (pin "3") (pinfunction "S_3") (pintype "passive"))
      (node (ref "U$32") (pin "5") (pinfunction "SENSE+_5") (pintype "bidirectional"))
      (node (ref "U$47") (pin "P$2") (pinfunction "2_P$2") (pintype "passive"))
    )
    (net (code "70") (name "Net-(Q6-G)") (class "Default")
      (node (ref "Q6") (pin "1") (pinfunction "G_1") (pintype "passive"))
      (node (ref "U$37") (pin "7") (pinfunction "GATE_7") (pintype "bidirectional"))
    )
    (net (code "71") (name "Net-(Q6-S)") (class "Default")
      (node (ref "Q6") (pin "3") (pinfunction "S_3") (pintype "passive"))
      (node (ref "U$37") (pin "5") (pinfunction "SENSE+_5") (pintype "bidirectional"))
      (node (ref "U$45") (pin "P$2") (pinfunction "2_P$2") (pintype "passive"))
    )
    (net (code "72") (name "Net-(Q7-G)") (class "Default")
      (node (ref "Q7") (pin "1") (pinfunction "G_1") (pintype "passive"))
      (node (ref "U$41") (pin "7") (pinfunction "GATE_7") (pintype "bidirectional"))
    )
    (net (code "73") (name "Net-(Q7-S)") (class "Default")
      (node (ref "Q7") (pin "3") (pinfunction "S_3") (pintype "passive"))
      (node (ref "U$41") (pin "5") (pinfunction "SENSE+_5") (pintype "bidirectional"))
      (node (ref "U$46") (pin "P$2") (pinfunction "2_P$2") (pintype "passive"))
    )
    (net (code "74") (name "Net-(Q9-A)") (class "Default")
      (node (ref "Q9") (pin "8") (pinfunction "A_8") (pintype "bidirectional"))
      (node (ref "R8") (pin "1") (pinfunction "1_1") (pintype "passive"))
      (node (ref "U$64") (pin "3") (pinfunction "3+RECEIVE+_3") (pintype "bidirectional"))
    )
    (net (code "75") (name "Net-(Q9-B)") (class "Default")
      (node (ref "Q9") (pin "7") (pinfunction "B_7") (pintype "bidirectional"))
      (node (ref "R8") (pin "2") (pinfunction "2_2") (pintype "passive"))
      (node (ref "U$64") (pin "6") (pinfunction "6-RECEIVE-_6") (pintype "bidirectional"))
    )
    (net (code "76") (name "Net-(Q9-D)") (class "Default")
      (node (ref "Q9") (pin "3") (pinfunction "D_3") (pintype "bidirectional"))
      (node (ref "U$57") (pin "3") (pinfunction "PD1_3") (pintype "bidirectional"))
    )
    (net (code "77") (name "Net-(Q9-R)") (class "Default")
      (node (ref "Q9") (pin "2") (pinfunction "R_2") (pintype "bidirectional"))
      (node (ref "U$57") (pin "2") (pinfunction "PD0_2") (pintype "bidirectional"))
    )
    (net (code "78") (name "Net-(Q9-Y)") (class "Default")
      (node (ref "Q9") (pin "5") (pinfunction "Y_5") (pintype "bidirectional"))
      (node (ref "R6") (pin "2") (pinfunction "2_2") (pintype "passive"))
      (node (ref "U$64") (pin "1") (pinfunction "1-TRANS+_1") (pintype "bidirectional"))
    )
    (net (code "79") (name "Net-(Q9-Z)") (class "Default")
      (node (ref "Q9") (pin "6") (pinfunction "Z_6") (pintype "bidirectional"))
      (node (ref "R6") (pin "1") (pinfunction "1_1") (pintype "passive"))
      (node (ref "U$64") (pin "2") (pinfunction "2-TRANS-_2") (pintype "bidirectional"))
    )
    (net (code "80") (name "Net-(Q10-G)") (class "Default")
      (node (ref "Q10") (pin "2") (pinfunction "G_2") (pintype "bidirectional"))
      (node (ref "R19") (pin "2") (pinfunction "2_2") (pintype "passive"))
    )
    (net (code "81") (name "Net-(Q11-D)") (class "Default")
      (node (ref "Q11") (pin "3") (pinfunction "D_3") (pintype "bidirectional"))
      (node (ref "ZAPDOS-20V") (pin "3") (pinfunction "INHIBIT_3") (pintype "bidirectional"))
    )
    (net (code "82") (name "Net-(Q11-G)") (class "Default")
      (node (ref "Q11") (pin "2") (pinfunction "G_2") (pintype "bidirectional"))
      (node (ref "R13") (pin "2") (pinfunction "2_2") (pintype "passive"))
    )
    (net (code "83") (name "Net-(Q12-G)") (class "Default")
      (node (ref "Q12") (pin "2") (pinfunction "G_2") (pintype "bidirectional"))
      (node (ref "R14") (pin "2") (pinfunction "2_2") (pintype "passive"))
    )
    (net (code "84") (name "Net-(Q14-G)") (class "Default")
      (node (ref "Q14") (pin "2") (pinfunction "G_2") (pintype "bidirectional"))
      (node (ref "R17") (pin "2") (pinfunction "2_2") (pintype "passive"))
    )
    (net (code "85") (name "Net-(Q15-G)") (class "Default")
      (node (ref "Q15") (pin "1") (pinfunction "G_1") (pintype "passive"))
      (node (ref "U$70") (pin "7") (pinfunction "GATE_7") (pintype "bidirectional"))
    )
    (net (code "86") (name "Net-(Q15-S)") (class "Default")
      (node (ref "Q15") (pin "3") (pinfunction "S_3") (pintype "passive"))
      (node (ref "U$70") (pin "5") (pinfunction "SENSE+_5") (pintype "bidirectional"))
      (node (ref "U$73") (pin "P$2") (pinfunction "2_P$2") (pintype "passive"))
    )
    (net (code "87") (name "Net-(Q16-HO)") (class "Default")
      (node (ref "Q16") (pin "7") (pinfunction "HO_7") (pintype "bidirectional"))
      (node (ref "R32") (pin "2") (pinfunction "2_2") (pintype "passive"))
    )
    (net (code "88") (name "Net-(Q16-IN)") (class "Default")
      (node (ref "Q16") (pin "2") (pinfunction "IN_2") (pintype "bidirectional"))
      (node (ref "R16") (pin "2") (pinfunction "2_2") (pintype "passive"))
    )
    (net (code "89") (name "Net-(Q17-REF2)") (class "Default")
      (node (ref "C20") (pin "1") (pinfunction "1_1") (pintype "passive"))
      (node (ref "Q17") (pin "3") (pinfunction "REF2_3") (pintype "bidirectional"))
      (node (ref "Q17") (pin "6") (pinfunction "V+_6") (pintype "bidirectional"))
      (node (ref "R11") (pin "1") (pinfunction "1_1") (pintype "passive"))
    )
    (net (code "90") (name "Net-(RAICHU-5V-CRIT-ADJUST)") (class "Default")
      (node (ref "R3") (pin "2") (pinfunction "2_2") (pintype "passive"))
      (node (ref "RAICHU-5V-CRIT") (pin "4") (pinfunction "ADJUST_4") (pintype "bidirectional"))
    )
    (net (code "91") (name "Net-(RAICHU-5V-CRIT-SENSE)") (class "Default")
      (node (ref "C15") (pin "+") (pinfunction "+_+") (pintype "passive"))
      (node (ref "L4") (pin "1") (pinfunction "1_1") (pintype "bidirectional"))
      (node (ref "L4") (pin "2") (pinfunction "2_2") (pintype "bidirectional"))
      (node (ref "L4") (pin "3") (pinfunction "3_3") (pintype "bidirectional"))
      (node (ref "L4") (pin "4") (pinfunction "4_4") (pintype "bidirectional"))
      (node (ref "RAICHU-5V-CRIT") (pin "5") (pinfunction "SENSE_5") (pintype "bidirectional"))
      (node (ref "RAICHU-5V-CRIT") (pin "6") (pinfunction "VOUT_6") (pintype "bidirectional"))
    )
    (net (code "92") (name "Net-(RAICHU-5V-CRIT-VIN)") (class "Default")
      (node (ref "C4") (pin "2") (pinfunction "2_2") (pintype "passive"))
      (node (ref "L1") (pin "5") (pinfunction "5_5") (pintype "bidirectional"))
      (node (ref "L1") (pin "6") (pinfunction "6_6") (pintype "bidirectional"))
      (node (ref "L1") (pin "7") (pinfunction "7_7") (pintype "bidirectional"))
      (node (ref "L1") (pin "8") (pinfunction "8_8") (pintype "bidirectional"))
      (node (ref "RAICHU-5V-CRIT") (pin "2") (pinfunction "VIN_2") (pintype "bidirectional"))
    )
    (net (code "93") (name "Net-(U$11-CT)") (class "Default")
      (node (ref "C41") (pin "1") (pinfunction "1_1") (pintype "passive"))
      (node (ref "U$11") (pin "3") (pinfunction "CT_3") (pintype "bidirectional"))
    )
    (net (code "94") (name "Net-(U$11-INPUT)") (class "Default")
      (node (ref "R18") (pin "2") (pinfunction "2_2") (pintype "passive"))
      (node (ref "U$11") (pin "2") (pinfunction "INPUT_2") (pintype "bidirectional"))
    )
    (net (code "95") (name "Net-(U$11-SENSE-)") (class "Default")
      (node (ref "U$11") (pin "6") (pinfunction "SENSE-_6") (pintype "bidirectional"))
      (node (ref "U$14") (pin "P$1") (pinfunction "P$1_P$1") (pintype "bidirectional"))
      (node (ref "U$49") (pin "P$1") (pinfunction "1_P$1") (pintype "passive"))
    )
    (net (code "96") (name "Net-(U$11-VBOOST)") (class "Default")
      (node (ref "C35") (pin "2") (pinfunction "2_2") (pintype "passive"))
      (node (ref "U$11") (pin "8") (pinfunction "VBOOST_8") (pintype "bidirectional"))
    )
    (net (code "97") (name "Net-(U$13-OUT)") (class "Default")
      (node (ref "U$13") (pin "2") (pinfunction "OUT_2") (pintype "bidirectional"))
      (node (ref "U$57") (pin "23") (pinfunction "PC0_23") (pintype "bidirectional"))
    )
    (net (code "98") (name "Net-(U$23-CT)") (class "Default")
      (node (ref "C37") (pin "1") (pinfunction "1_1") (pintype "passive"))
      (node (ref "U$23") (pin "3") (pinfunction "CT_3") (pintype "bidirectional"))
    )
    (net (code "99") (name "Net-(U$23-INPUT)") (class "Default")
      (node (ref "R23") (pin "2") (pinfunction "2_2") (pintype "passive"))
      (node (ref "U$23") (pin "2") (pinfunction "INPUT_2") (pintype "bidirectional"))
    )
    (net (code "100") (name "Net-(U$23-SENSE-)") (class "Default")
      (node (ref "U$23") (pin "6") (pinfunction "SENSE-_6") (pintype "bidirectional"))
      (node (ref "U$26") (pin "P$1") (pinfunction "P$1_P$1") (pintype "bidirectional"))
      (node (ref "U$50") (pin "P$1") (pinfunction "1_P$1") (pintype "passive"))
    )
    (net (code "101") (name "Net-(U$23-VBOOST)") (class "Default")
      (node (ref "C31") (pin "2") (pinfunction "2_2") (pintype "passive"))
      (node (ref "U$23") (pin "8") (pinfunction "VBOOST_8") (pintype "bidirectional"))
    )
    (net (code "102") (name "Net-(U$27-CT)") (class "Default")
      (node (ref "C40") (pin "1") (pinfunction "1_1") (pintype "passive"))
      (node (ref "U$27") (pin "3") (pinfunction "CT_3") (pintype "bidirectional"))
    )
    (net (code "103") (name "Net-(U$27-INPUT)") (class "Default")
      (node (ref "R15") (pin "2") (pinfunction "2_2") (pintype "passive"))
      (node (ref "U$27") (pin "2") (pinfunction "INPUT_2") (pintype "bidirectional"))
    )
    (net (code "104") (name "Net-(U$27-SENSE-)") (class "Default")
      (node (ref "U$27") (pin "6") (pinfunction "SENSE-_6") (pintype "bidirectional"))
      (node (ref "U$31") (pin "P$1") (pinfunction "P$1_P$1") (pintype "bidirectional"))
      (node (ref "U$48") (pin "P$1") (pinfunction "1_P$1") (pintype "passive"))
    )
    (net (code "105") (name "Net-(U$27-VBOOST)") (class "Default")
      (node (ref "C34") (pin "2") (pinfunction "2_2") (pintype "passive"))
      (node (ref "U$27") (pin "8") (pinfunction "VBOOST_8") (pintype "bidirectional"))
    )
    (net (code "106") (name "Net-(U$32-CT)") (class "Default")
      (node (ref "C36") (pin "1") (pinfunction "1_1") (pintype "passive"))
      (node (ref "U$32") (pin "3") (pinfunction "CT_3") (pintype "bidirectional"))
    )
    (net (code "107") (name "Net-(U$32-INPUT)") (class "Default")
      (node (ref "R22") (pin "2") (pinfunction "2_2") (pintype "passive"))
      (node (ref "U$32") (pin "2") (pinfunction "INPUT_2") (pintype "bidirectional"))
    )
    (net (code "108") (name "Net-(U$32-SENSE-)") (class "Default")
      (node (ref "U$32") (pin "6") (pinfunction "SENSE-_6") (pintype "bidirectional"))
      (node (ref "U$36") (pin "P$1") (pinfunction "P$1_P$1") (pintype "bidirectional"))
      (node (ref "U$47") (pin "P$1") (pinfunction "1_P$1") (pintype "passive"))
    )
    (net (code "109") (name "Net-(U$32-VBOOST)") (class "Default")
      (node (ref "C30") (pin "2") (pinfunction "2_2") (pintype "passive"))
      (node (ref "U$32") (pin "8") (pinfunction "VBOOST_8") (pintype "bidirectional"))
    )
    (net (code "110") (name "Net-(U$37-CT)") (class "Default")
      (node (ref "C39") (pin "1") (pinfunction "1_1") (pintype "passive"))
      (node (ref "U$37") (pin "3") (pinfunction "CT_3") (pintype "bidirectional"))
    )
    (net (code "111") (name "Net-(U$37-INPUT)") (class "Default")
      (node (ref "R20") (pin "2") (pinfunction "2_2") (pintype "passive"))
      (node (ref "U$37") (pin "2") (pinfunction "INPUT_2") (pintype "bidirectional"))
    )
    (net (code "112") (name "Net-(U$37-SENSE-)") (class "Default")
      (node (ref "U$37") (pin "6") (pinfunction "SENSE-_6") (pintype "bidirectional"))
      (node (ref "U$40") (pin "P$1") (pinfunction "P$1_P$1") (pintype "bidirectional"))
      (node (ref "U$45") (pin "P$1") (pinfunction "1_P$1") (pintype "passive"))
    )
    (net (code "113") (name "Net-(U$37-VBOOST)") (class "Default")
      (node (ref "C33") (pin "2") (pinfunction "2_2") (pintype "passive"))
      (node (ref "U$37") (pin "8") (pinfunction "VBOOST_8") (pintype "bidirectional"))
    )
    (net (code "114") (name "Net-(U$41-CT)") (class "Default")
      (node (ref "C38") (pin "1") (pinfunction "1_1") (pintype "passive"))
      (node (ref "U$41") (pin "3") (pinfunction "CT_3") (pintype "bidirectional"))
    )
    (net (code "115") (name "Net-(U$41-INPUT)") (class "Default")
      (node (ref "R21") (pin "2") (pinfunction "2_2") (pintype "passive"))
      (node (ref "U$41") (pin "2") (pinfunction "INPUT_2") (pintype "bidirectional"))
    )
    (net (code "116") (name "Net-(U$41-SENSE-)") (class "Default")
      (node (ref "U$41") (pin "6") (pinfunction "SENSE-_6") (pintype "bidirectional"))
      (node (ref "U$44") (pin "P$1") (pinfunction "P$1_P$1") (pintype "bidirectional"))
      (node (ref "U$46") (pin "P$1") (pinfunction "1_P$1") (pintype "passive"))
    )
    (net (code "117") (name "Net-(U$41-VBOOST)") (class "Default")
      (node (ref "C32") (pin "2") (pinfunction "2_2") (pintype "passive"))
      (node (ref "U$41") (pin "8") (pinfunction "VBOOST_8") (pintype "bidirectional"))
    )
    (net (code "118") (name "Net-(U$57-XTAL1)") (class "Default")
      (node (ref "C5") (pin "2") (pinfunction "2_2") (pintype "passive"))
      (node (ref "U$57") (pin "9") (pinfunction "XTAL1_9") (pintype "bidirectional"))
      (node (ref "X1") (pin "P$2") (pinfunction "2_P$2") (pintype "passive"))
    )
    (net (code "119") (name "Net-(U$57-XTAL2)") (class "Default")
      (node (ref "C6") (pin "2") (pinfunction "2_2") (pintype "passive"))
      (node (ref "U$57") (pin "10") (pinfunction "XTAL2_10") (pintype "bidirectional"))
      (node (ref "X1") (pin "P$1") (pinfunction "1_P$1") (pintype "passive"))
    )
    (net (code "120") (name "Net-(U$70-CT)") (class "Default")
      (node (ref "C49") (pin "1") (pinfunction "1_1") (pintype "passive"))
      (node (ref "U$70") (pin "3") (pinfunction "CT_3") (pintype "bidirectional"))
    )
    (net (code "121") (name "Net-(U$70-INPUT)") (class "Default")
      (node (ref "R24") (pin "2") (pinfunction "2_2") (pintype "passive"))
      (node (ref "U$70") (pin "2") (pinfunction "INPUT_2") (pintype "bidirectional"))
    )
    (net (code "122") (name "Net-(U$70-SENSE-)") (class "Default")
      (node (ref "U$70") (pin "6") (pinfunction "SENSE-_6") (pintype "bidirectional"))
      (node (ref "U$72") (pin "P$1") (pinfunction "P$1_P$1") (pintype "bidirectional"))
      (node (ref "U$73") (pin "P$1") (pinfunction "1_P$1") (pintype "passive"))
    )
    (net (code "123") (name "Net-(U$70-VBOOST)") (class "Default")
      (node (ref "C48") (pin "2") (pinfunction "2_2") (pintype "passive"))
      (node (ref "U$70") (pin "8") (pinfunction "VBOOST_8") (pintype "bidirectional"))
    )
    (net (code "124") (name "Net-(ZAPDOS-20V-ADJUST)") (class "Default")
      (node (ref "R12") (pin "2") (pinfunction "2_2") (pintype "passive"))
      (node (ref "ZAPDOS-20V") (pin "4") (pinfunction "ADJUST_4") (pintype "bidirectional"))
    )
    (net (code "125") (name "Net-(ZAPDOS-20V-SENSE)") (class "Default")
      (node (ref "C17") (pin "+") (pinfunction "+_+") (pintype "passive"))
      (node (ref "L10") (pin "1") (pinfunction "1_1") (pintype "bidirectional"))
      (node (ref "L10") (pin "2") (pinfunction "2_2") (pintype "bidirectional"))
      (node (ref "L10") (pin "3") (pinfunction "3_3") (pintype "bidirectional"))
      (node (ref "L10") (pin "4") (pinfunction "4_4") (pintype "bidirectional"))
      (node (ref "ZAPDOS-20V") (pin "5") (pinfunction "SENSE_5") (pintype "bidirectional"))
      (node (ref "ZAPDOS-20V") (pin "6") (pinfunction "VOUT_6") (pintype "bidirectional"))
    )
    (net (code "126") (name "Net-(ZAPDOS-20V-VIN)") (class "Default")
      (node (ref "C29") (pin "2") (pinfunction "2_2") (pintype "passive"))
      (node (ref "L9") (pin "5") (pinfunction "5_5") (pintype "bidirectional"))
      (node (ref "L9") (pin "6") (pinfunction "6_6") (pintype "bidirectional"))
      (node (ref "L9") (pin "7") (pinfunction "7_7") (pintype "bidirectional"))
      (node (ref "L9") (pin "8") (pinfunction "8_8") (pintype "bidirectional"))
      (node (ref "ZAPDOS-20V") (pin "2") (pinfunction "VIN_2") (pintype "bidirectional"))
    )
    (net (code "127") (name "S_12V-2") (class "Default")
      (node (ref "R14") (pin "1") (pinfunction "1_1") (pintype "passive"))
      (node (ref "U$57") (pin "6") (pinfunction "PD4_6") (pintype "bidirectional"))
    )
    (net (code "128") (name "S_MAIN") (class "Default")
      (node (ref "R16") (pin "1") (pinfunction "1_1") (pintype "passive"))
      (node (ref "U$57") (pin "4") (pinfunction "PD2_4") (pintype "bidirectional"))
    )
    (net (code "129") (name "S_MC1") (class "Default")
      (node (ref "R22") (pin "1") (pinfunction "1_1") (pintype "passive"))
      (node (ref "U$57") (pin "14") (pinfunction "PB0_14") (pintype "bidirectional"))
    )
    (net (code "130") (name "S_MC2") (class "Default")
      (node (ref "R21") (pin "1") (pinfunction "1_1") (pintype "passive"))
      (node (ref "U$57") (pin "13") (pinfunction "PD7_13") (pintype "bidirectional"))
    )
    (net (code "131") (name "S_MC3") (class "Default")
      (node (ref "R20") (pin "1") (pinfunction "1_1") (pintype "passive"))
      (node (ref "U$57") (pin "12") (pinfunction "PD6_12") (pintype "bidirectional"))
    )
    (net (code "132") (name "S_MC4") (class "Default")
      (node (ref "R18") (pin "1") (pinfunction "1_1") (pintype "passive"))
      (node (ref "U$57") (pin "11") (pinfunction "PD5_11") (pintype "bidirectional"))
    )
    (net (code "133") (name "S_MC5") (class "Default")
      (node (ref "R15") (pin "1") (pinfunction "1_1") (pintype "passive"))
      (node (ref "U$57") (pin "16") (pinfunction "PB2_16") (pintype "bidirectional"))
    )
    (net (code "134") (name "S_MC6") (class "Default")
      (node (ref "R23") (pin "1") (pinfunction "1_1") (pintype "passive"))
      (node (ref "U$57") (pin "17") (pinfunction "PB3_17") (pintype "bidirectional"))
    )
    (net (code "135") (name "S_POE") (class "Default")
      (node (ref "R13") (pin "1") (pinfunction "1_1") (pintype "passive"))
      (node (ref "U$57") (pin "5") (pinfunction "PD3_5") (pintype "bidirectional"))
    )
    (net (code "136") (name "S_V5-2") (class "Default")
      (node (ref "R17") (pin "1") (pinfunction "1_1") (pintype "passive"))
      (node (ref "U$57") (pin "18") (pinfunction "PB4_18") (pintype "bidirectional"))
    )
    (net (code "137") (name "S_V12-1") (class "Default")
      (node (ref "R19") (pin "1") (pinfunction "1_1") (pintype "passive"))
      (node (ref "U$57") (pin "19") (pinfunction "PB5_19") (pintype "bidirectional"))
    )
    (net (code "138") (name "S_V24AUX") (class "Default")
      (node (ref "R24") (pin "1") (pinfunction "1_1") (pintype "passive"))
      (node (ref "U$57") (pin "15") (pinfunction "PB1_15") (pintype "bidirectional"))
    )
    (net (code "139") (name "V1") (class "Default")
      (node (ref "C16") (pin "1") (pinfunction "1_1") (pintype "passive"))
      (node (ref "C55") (pin "1") (pinfunction "1_1") (pintype "passive"))
      (node (ref "D5") (pin "C") (pinfunction "K_C") (pintype "passive"))
      (node (ref "J2") (pin "PIN1-1") (pinfunction "1-1_PIN1-1") (pintype "bidirectional"))
      (node (ref "J2") (pin "PIN1-2") (pinfunction "1-2_PIN1-2") (pintype "bidirectional"))
      (node (ref "Q13") (pin "4") (pinfunction "P$1_4") (pintype "bidirectional"))
      (node (ref "Q18") (pin "1") (pinfunction "VIN_1") (pintype "bidirectional"))
      (node (ref "Q2") (pin "4") (pinfunction "P$1_4") (pintype "bidirectional"))
      (node (ref "Q8") (pin "1") (pinfunction "VIN_1") (pintype "bidirectional"))
      (node (ref "R25") (pin "1") (pinfunction "1_1") (pintype "passive"))
    )
    (net (code "140") (name "V24") (class "Default")
      (node (ref "C10") (pin "2") (pinfunction "2_2") (pintype "passive"))
      (node (ref "C19") (pin "2") (pinfunction "2_2") (pintype "passive"))
      (node (ref "C24") (pin "2") (pinfunction "2_2") (pintype "passive"))
      (node (ref "C28") (pin "2") (pinfunction "2_2") (pintype "passive"))
      (node (ref "C30") (pin "1") (pinfunction "1_1") (pintype "passive"))
      (node (ref "C31") (pin "1") (pinfunction "1_1") (pintype "passive"))
      (node (ref "C32") (pin "1") (pinfunction "1_1") (pintype "passive"))
      (node (ref "C33") (pin "1") (pinfunction "1_1") (pintype "passive"))
      (node (ref "C34") (pin "1") (pinfunction "1_1") (pintype "passive"))
      (node (ref "C35") (pin "1") (pinfunction "1_1") (pintype "passive"))
      (node (ref "C42") (pin "1") (pinfunction "1_1") (pintype "passive"))
      (node (ref "C43") (pin "1") (pinfunction "1_1") (pintype "passive"))
      (node (ref "C44") (pin "1") (pinfunction "1_1") (pintype "passive"))
      (node (ref "C45") (pin "1") (pinfunction "1_1") (pintype "passive"))
      (node (ref "C46") (pin "1") (pinfunction "1_1") (pintype "passive"))
      (node (ref "C47") (pin "1") (pinfunction "1_1") (pintype "passive"))
      (node (ref "C48") (pin "1") (pinfunction "1_1") (pintype "passive"))
      (node (ref "C50") (pin "1") (pinfunction "1_1") (pintype "passive"))
      (node (ref "C58") (pin "P$1") (pinfunction "+_P$1") (pintype "passive"))
      (node (ref "C59") (pin "P$1") (pinfunction "+_P$1") (pintype "passive"))
      (node (ref "C60") (pin "P$1") (pinfunction "+_P$1") (pintype "passive"))
      (node (ref "C61") (pin "P$1") (pinfunction "+_P$1") (pintype "passive"))
      (node (ref "C62") (pin "P$1") (pinfunction "+_P$1") (pintype "passive"))
      (node (ref "C63") (pin "P$1") (pinfunction "+_P$1") (pintype "passive"))
      (node (ref "C64") (pin "P$1") (pinfunction "+_P$1") (pintype "passive"))
      (node (ref "C65") (pin "P$1") (pinfunction "+_P$1") (pintype "passive"))
      (node (ref "C66") (pin "P$1") (pinfunction "+_P$1") (pintype "passive"))
      (node (ref "C67") (pin "P$1") (pinfunction "+_P$1") (pintype "passive"))
      (node (ref "C77") (pin "P$1") (pinfunction "+_P$1") (pintype "passive"))
      (node (ref "C78") (pin "P$1") (pinfunction "+_P$1") (pintype "passive"))
      (node (ref "C79") (pin "P$1") (pinfunction "+_P$1") (pintype "passive"))
      (node (ref "C9") (pin "2") (pinfunction "2_2") (pintype "passive"))
      (node (ref "D10") (pin "C") (pinfunction "K_C") (pintype "passive"))
      (node (ref "D4") (pin "C") (pinfunction "K_C") (pintype "passive"))
      (node (ref "L1") (pin "1") (pinfunction "1_1") (pintype "bidirectional"))
      (node (ref "L1") (pin "2") (pinfunction "2_2") (pintype "bidirectional"))
      (node (ref "L1") (pin "3") (pinfunction "3_3") (pintype "bidirectional"))
      (node (ref "L1") (pin "4") (pinfunction "4_4") (pintype "bidirectional"))
      (node (ref "L2") (pin "1") (pinfunction "1_1") (pintype "bidirectional"))
      (node (ref "L2") (pin "2") (pinfunction "2_2") (pintype "bidirectional"))
      (node (ref "L2") (pin "3") (pinfunction "3_3") (pintype "bidirectional"))
      (node (ref "L2") (pin "4") (pinfunction "4_4") (pintype "bidirectional"))
      (node (ref "L5") (pin "1") (pinfunction "1_1") (pintype "bidirectional"))
      (node (ref "L5") (pin "2") (pinfunction "2_2") (pintype "bidirectional"))
      (node (ref "L5") (pin "3") (pinfunction "3_3") (pintype "bidirectional"))
      (node (ref "L5") (pin "4") (pinfunction "4_4") (pintype "bidirectional"))
      (node (ref "L7") (pin "1") (pinfunction "1_1") (pintype "bidirectional"))
      (node (ref "L7") (pin "2") (pinfunction "2_2") (pintype "bidirectional"))
      (node (ref "L7") (pin "3") (pinfunction "3_3") (pintype "bidirectional"))
      (node (ref "L7") (pin "4") (pinfunction "4_4") (pintype "bidirectional"))
      (node (ref "L9") (pin "1") (pinfunction "1_1") (pintype "bidirectional"))
      (node (ref "L9") (pin "2") (pinfunction "2_2") (pintype "bidirectional"))
      (node (ref "L9") (pin "3") (pinfunction "3_3") (pintype "bidirectional"))
      (node (ref "L9") (pin "4") (pinfunction "4_4") (pintype "bidirectional"))
      (node (ref "Q1") (pin "2") (pinfunction "D_2") (pintype "passive"))
      (node (ref "Q15") (pin "2") (pinfunction "D_2") (pintype "passive"))
      (node (ref "Q3") (pin "2") (pinfunction "D_2") (pintype "passive"))
      (node (ref "Q4") (pin "2") (pinfunction "D_2") (pintype "passive"))
      (node (ref "Q5") (pin "2") (pinfunction "D_2") (pintype "passive"))
      (node (ref "Q6") (pin "2") (pinfunction "D_2") (pintype "passive"))
      (node (ref "Q7") (pin "2") (pinfunction "D_2") (pintype "passive"))
      (node (ref "R7") (pin "2") (pinfunction "2_2") (pintype "passive"))
      (node (ref "U$11") (pin "1") (pinfunction "VDD_1") (pintype "bidirectional"))
      (node (ref "U$23") (pin "1") (pinfunction "VDD_1") (pintype "bidirectional"))
      (node (ref "U$27") (pin "1") (pinfunction "VDD_1") (pintype "bidirectional"))
      (node (ref "U$32") (pin "1") (pinfunction "VDD_1") (pintype "bidirectional"))
      (node (ref "U$37") (pin "1") (pinfunction "VDD_1") (pintype "bidirectional"))
      (node (ref "U$41") (pin "1") (pinfunction "VDD_1") (pintype "bidirectional"))
      (node (ref "U$70") (pin "1") (pinfunction "VDD_1") (pintype "bidirectional"))
    )
    (net (code "141") (name "VA5") (class "Default")
      (node (ref "C11") (pin "1") (pinfunction "1_1") (pintype "passive"))
      (node (ref "C12") (pin "2") (pinfunction "2_2") (pintype "passive"))
      (node (ref "C13") (pin "1") (pinfunction "1_1") (pintype "passive"))
      (node (ref "C51") (pin "2") (pinfunction "2_2") (pintype "passive"))
      (node (ref "Q8") (pin "3") (pinfunction "VOUT_3") (pintype "bidirectional"))
      (node (ref "Q9") (pin "1") (pinfunction "VCC_1") (pintype "bidirectional"))
      (node (ref "R1") (pin "2") (pinfunction "2_2") (pintype "passive"))
      (node (ref "R11") (pin "2") (pinfunction "2_2") (pintype "passive"))
      (node (ref "U$13") (pin "1") (pinfunction "VIN_1") (pintype "bidirectional"))
      (node (ref "U$57") (pin "20") (pinfunction "AVCC_20") (pintype "bidirectional"))
      (node (ref "U$57") (pin "7") (pinfunction "VCC_7") (pintype "bidirectional"))
    )
    (net (code "142") (name "V_ANTENNA") (class "Default")
      (node (ref "C56") (pin "+") (pinfunction "+_+") (pintype "passive"))
      (node (ref "C57") (pin "1") (pinfunction "1_1") (pintype "passive"))
      (node (ref "D8") (pin "C") (pinfunction "K_C") (pintype "passive"))
      (node (ref "D9") (pin "C") (pinfunction "K_C") (pintype "passive"))
      (node (ref "N1") (pin "1-4") (pinfunction "4-DC+_1-4") (pintype "bidirectional"))
      (node (ref "N1") (pin "1-5") (pinfunction "5-DC++_1-5") (pintype "bidirectional"))
    )
    (net (code "143") (name "V_POE") (class "Default")
      (node (ref "C27") (pin "1") (pinfunction "1_1") (pintype "passive"))
      (node (ref "C68") (pin "1") (pinfunction "1_1") (pintype "passive"))
      (node (ref "C69") (pin "1") (pinfunction "1_1") (pintype "passive"))
      (node (ref "C70") (pin "1") (pinfunction "1_1") (pintype "passive"))
      (node (ref "D6") (pin "C") (pinfunction "K_C") (pintype "passive"))
      (node (ref "D8") (pin "A") (pinfunction "A_A") (pintype "passive"))
      (node (ref "L10") (pin "5") (pinfunction "5_5") (pintype "bidirectional"))
      (node (ref "L10") (pin "6") (pinfunction "6_6") (pintype "bidirectional"))
      (node (ref "L10") (pin "7") (pinfunction "7_7") (pintype "bidirectional"))
      (node (ref "L10") (pin "8") (pinfunction "8_8") (pintype "bidirectional"))
      (node (ref "N2") (pin "1-4") (pinfunction "4-DC+_1-4") (pintype "bidirectional"))
      (node (ref "N2") (pin "1-5") (pinfunction "5-DC++_1-5") (pintype "bidirectional"))
      (node (ref "N3") (pin "1-4") (pinfunction "4-DC+_1-4") (pintype "bidirectional"))
      (node (ref "N3") (pin "1-5") (pinfunction "5-DC++_1-5") (pintype "bidirectional"))
      (node (ref "N4") (pin "1-4") (pinfunction "4-DC+_1-4") (pintype "bidirectional"))
      (node (ref "N4") (pin "1-5") (pinfunction "5-DC++_1-5") (pintype "bidirectional"))
      (node (ref "N5") (pin "1-4") (pinfunction "4-DC+_1-4") (pintype "bidirectional"))
      (node (ref "N5") (pin "1-5") (pinfunction "5-DC++_1-5") (pintype "bidirectional"))
      (node (ref "N6") (pin "1-4") (pinfunction "4-DC+_1-4") (pintype "bidirectional"))
      (node (ref "N6") (pin "1-5") (pinfunction "5-DC++_1-5") (pintype "bidirectional"))
      (node (ref "N7") (pin "1-4") (pinfunction "4-DC+_1-4") (pintype "bidirectional"))
      (node (ref "N7") (pin "1-5") (pinfunction "5-DC++_1-5") (pintype "bidirectional"))
      (node (ref "N8") (pin "1-4") (pinfunction "4-DC+_1-4") (pintype "bidirectional"))
      (node (ref "N8") (pin "1-5") (pinfunction "5-DC++_1-5") (pintype "bidirectional"))
    )
    (net (code "144") (name "unconnected-(D9-PadA)") (class "Default")
      (node (ref "D9") (pin "A") (pinfunction "A_A") (pintype "passive"))
    )
    (net (code "145") (name "unconnected-(H1-Pad1)") (class "Default")
      (node (ref "H1") (pin "1") (pinfunction "1_1") (pintype "passive"))
    )
    (net (code "146") (name "unconnected-(H2-Pad1)") (class "Default")
      (node (ref "H2") (pin "1") (pinfunction "1_1") (pintype "passive"))
    )
    (net (code "147") (name "unconnected-(H3-Pad1)") (class "Default")
      (node (ref "H3") (pin "1") (pinfunction "1_1") (pintype "passive"))
    )
    (net (code "148") (name "unconnected-(H4-Pad1)") (class "Default")
      (node (ref "H4") (pin "1") (pinfunction "1_1") (pintype "passive"))
    )
    (net (code "149") (name "unconnected-(N1B-4-DC+-Pad2-4)") (class "Default")
      (node (ref "N1") (pin "2-4") (pinfunction "4-DC+_2-4") (pintype "bidirectional"))
    )
    (net (code "150") (name "unconnected-(N1B-5-DC++-Pad2-5)") (class "Default")
      (node (ref "N1") (pin "2-5") (pinfunction "5-DC++_2-5") (pintype "bidirectional"))
    )
    (net (code "151") (name "unconnected-(N2B-4-DC+-Pad2-4)") (class "Default")
      (node (ref "N2") (pin "2-4") (pinfunction "4-DC+_2-4") (pintype "bidirectional"))
    )
    (net (code "152") (name "unconnected-(N2B-5-DC++-Pad2-5)") (class "Default")
      (node (ref "N2") (pin "2-5") (pinfunction "5-DC++_2-5") (pintype "bidirectional"))
    )
    (net (code "153") (name "unconnected-(N3B-4-DC+-Pad2-4)") (class "Default")
      (node (ref "N3") (pin "2-4") (pinfunction "4-DC+_2-4") (pintype "bidirectional"))
    )
    (net (code "154") (name "unconnected-(N3B-5-DC++-Pad2-5)") (class "Default")
      (node (ref "N3") (pin "2-5") (pinfunction "5-DC++_2-5") (pintype "bidirectional"))
    )
    (net (code "155") (name "unconnected-(N4B-4-DC+-Pad2-4)") (class "Default")
      (node (ref "N4") (pin "2-4") (pinfunction "4-DC+_2-4") (pintype "bidirectional"))
    )
    (net (code "156") (name "unconnected-(N4B-5-DC++-Pad2-5)") (class "Default")
      (node (ref "N4") (pin "2-5") (pinfunction "5-DC++_2-5") (pintype "bidirectional"))
    )
    (net (code "157") (name "unconnected-(N5B-4-DC+-Pad2-4)") (class "Default")
      (node (ref "N5") (pin "2-4") (pinfunction "4-DC+_2-4") (pintype "bidirectional"))
    )
    (net (code "158") (name "unconnected-(N5B-5-DC++-Pad2-5)") (class "Default")
      (node (ref "N5") (pin "2-5") (pinfunction "5-DC++_2-5") (pintype "bidirectional"))
    )
    (net (code "159") (name "unconnected-(N6B-4-DC+-Pad2-4)") (class "Default")
      (node (ref "N6") (pin "2-4") (pinfunction "4-DC+_2-4") (pintype "bidirectional"))
    )
    (net (code "160") (name "unconnected-(N6B-5-DC++-Pad2-5)") (class "Default")
      (node (ref "N6") (pin "2-5") (pinfunction "5-DC++_2-5") (pintype "bidirectional"))
    )
    (net (code "161") (name "unconnected-(N7B-4-DC+-Pad2-4)") (class "Default")
      (node (ref "N7") (pin "2-4") (pinfunction "4-DC+_2-4") (pintype "bidirectional"))
    )
    (net (code "162") (name "unconnected-(N7B-5-DC++-Pad2-5)") (class "Default")
      (node (ref "N7") (pin "2-5") (pinfunction "5-DC++_2-5") (pintype "bidirectional"))
    )
    (net (code "163") (name "unconnected-(N8B-4-DC+-Pad2-4)") (class "Default")
      (node (ref "N8") (pin "2-4") (pinfunction "4-DC+_2-4") (pintype "bidirectional"))
    )
    (net (code "164") (name "unconnected-(N8B-5-DC++-Pad2-5)") (class "Default")
      (node (ref "N8") (pin "2-5") (pinfunction "5-DC++_2-5") (pintype "bidirectional"))
    )
    (net (code "165") (name "unconnected-(Q2-D-Pad2)") (class "Default")
      (node (ref "Q2") (pin "2") (pinfunction "D_2") (pintype "bidirectional"))
    )
    (net (code "166") (name "unconnected-(Q13-D-Pad2)") (class "Default")
      (node (ref "Q13") (pin "2") (pinfunction "D_2") (pintype "bidirectional"))
    )
    (net (code "167") (name "unconnected-(RAICHU-5V-CRIT-INHIBIT-Pad3)") (class "Default")
      (node (ref "RAICHU-5V-CRIT") (pin "3") (pinfunction "INHIBIT_3") (pintype "bidirectional"))
    )
    (net (code "168") (name "unconnected-(U$57-AREF-Pad21)") (class "Default")
      (node (ref "U$57") (pin "21") (pinfunction "AREF_21") (pintype "bidirectional"))
    )
    (net (code "169") (name "unconnected-(U$64-4-DC+-Pad4)") (class "Default")
      (node (ref "U$64") (pin "4") (pinfunction "4-DC+_4") (pintype "bidirectional"))
    )
    (net (code "170") (name "unconnected-(U$64-5-DC++-Pad5)") (class "Default")
      (node (ref "U$64") (pin "5") (pinfunction "5-DC++_5") (pintype "bidirectional"))
    )
  )
)
